# HandHeld_Terminal_V2_Rev3.net
KiCad netlist of a schematic drawn in Altium Designer
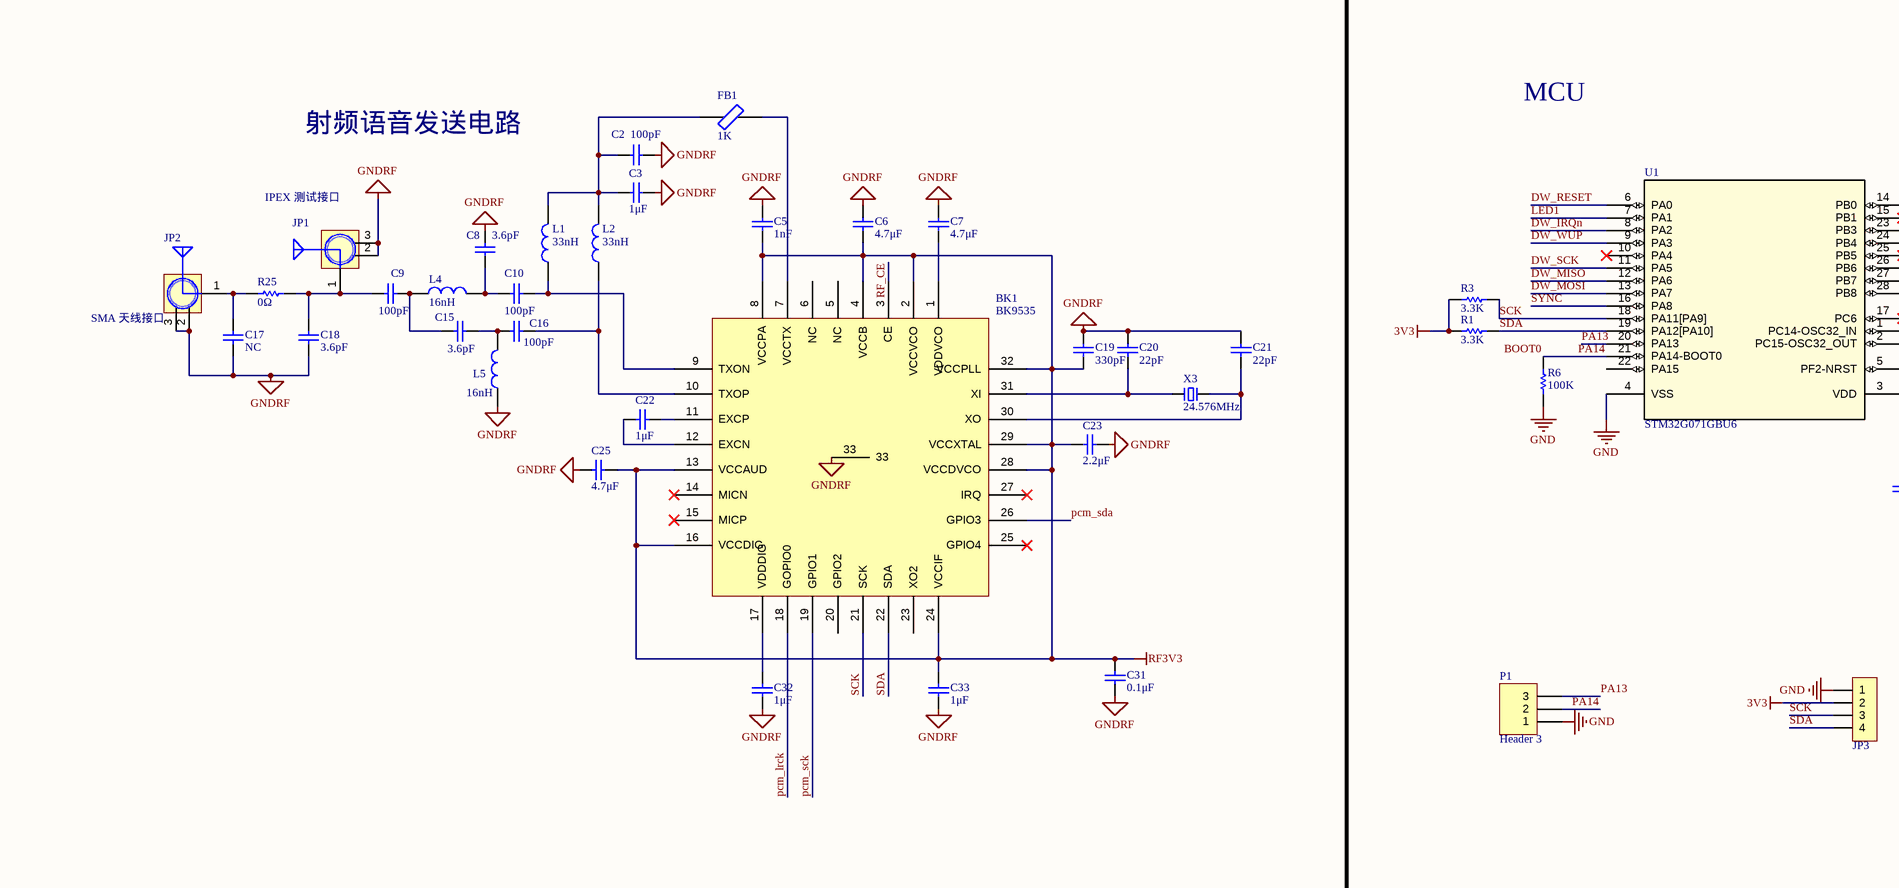
[diagram p0: HandHeld_Terminal_V2_Rev3.SchDoc, top left]
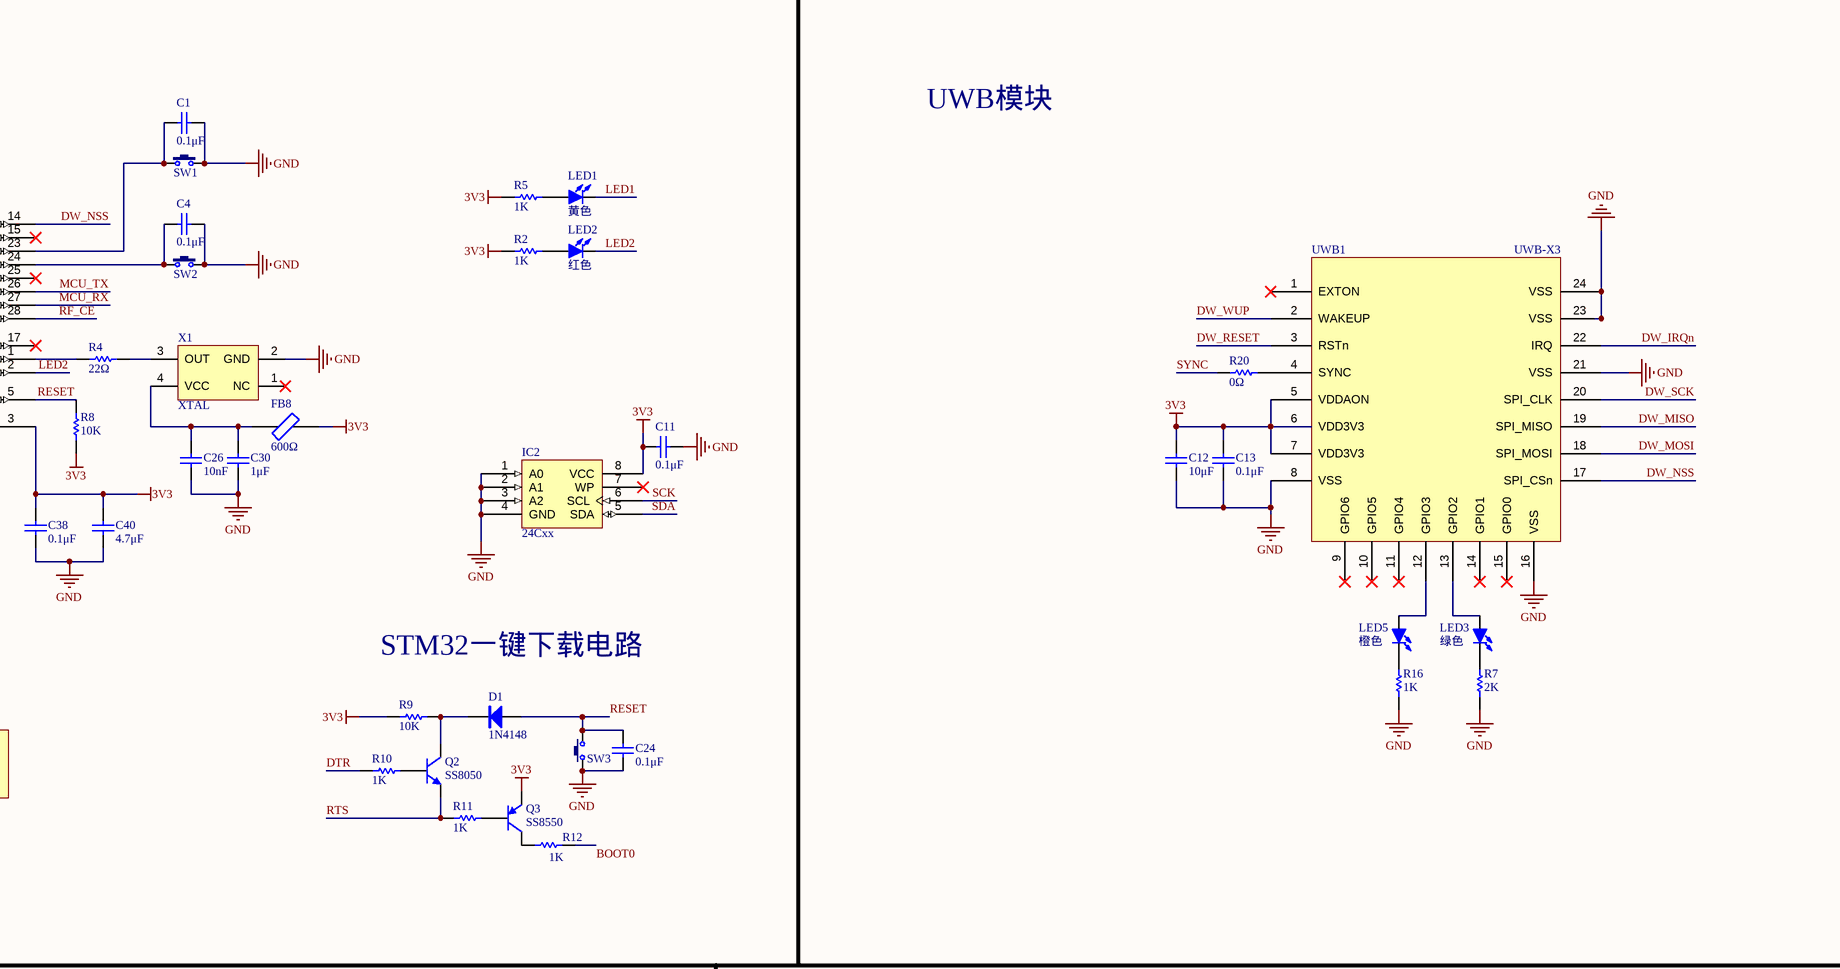
[diagram p1: HandHeld_Terminal_V2_Rev3.SchDoc, top right]
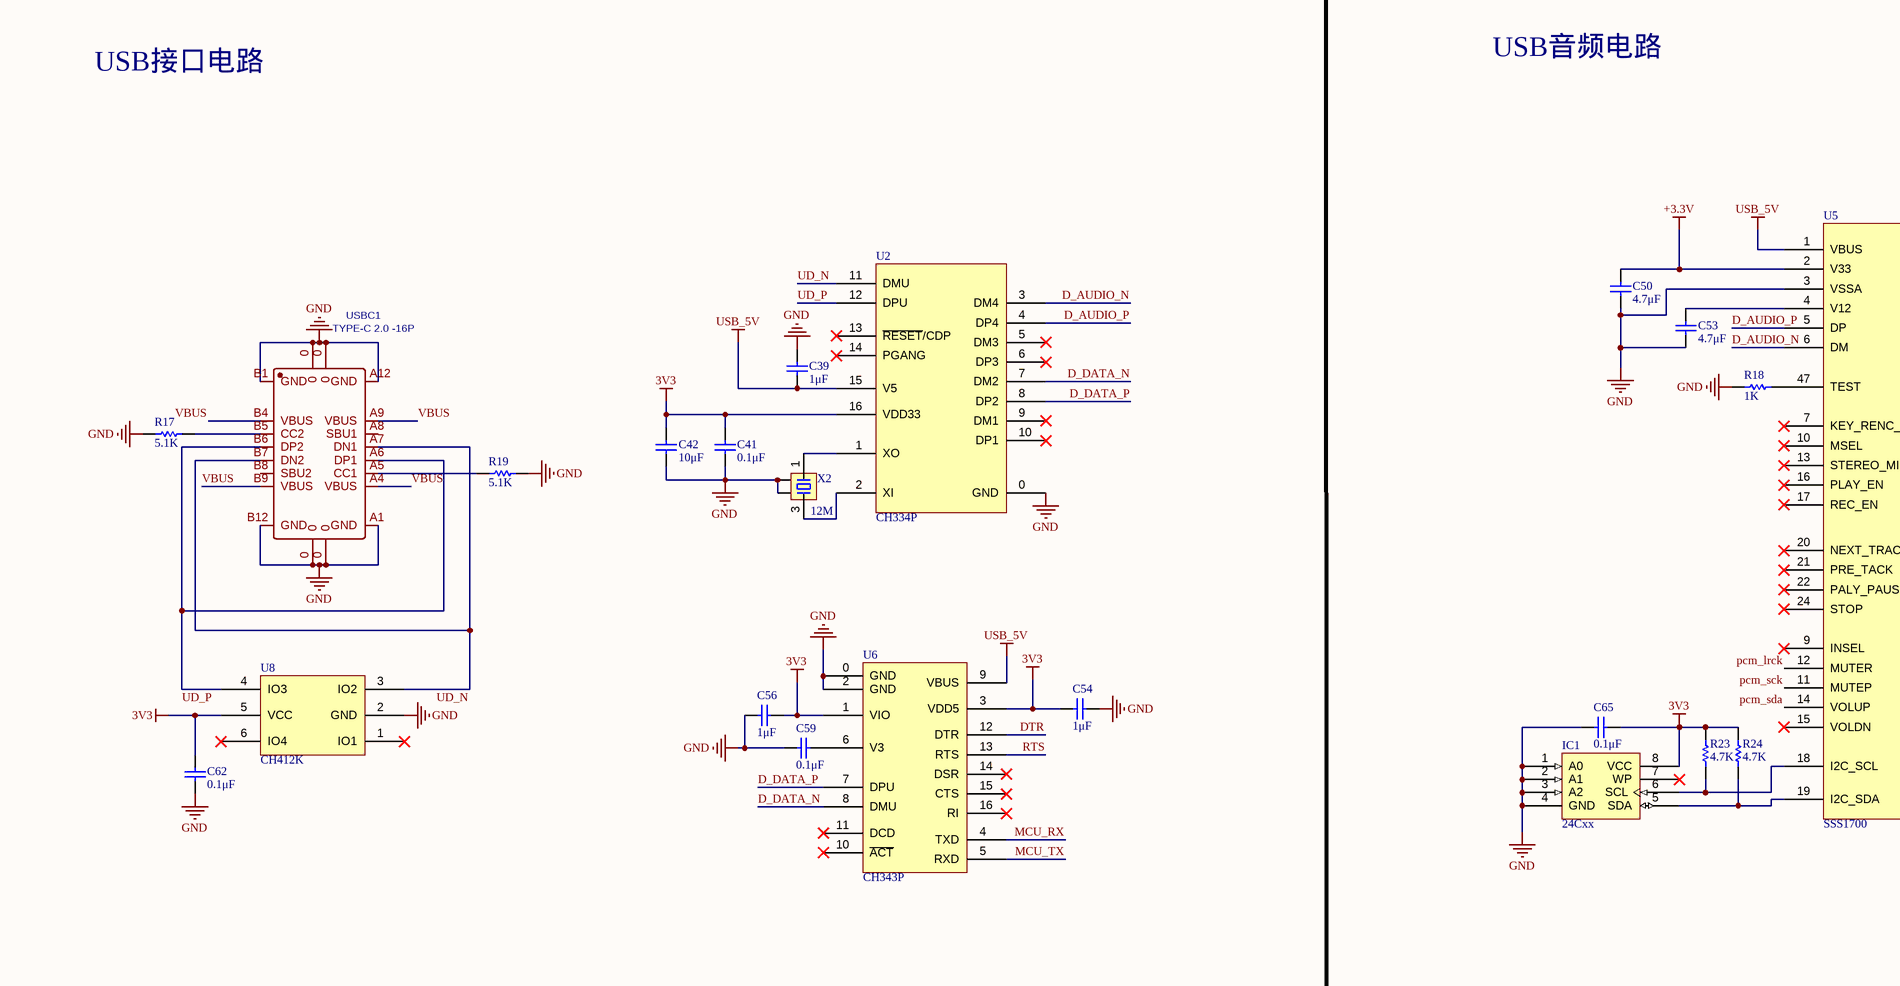
[diagram p2: HandHeld_Terminal_V2_Rev3.SchDoc, bottom left]
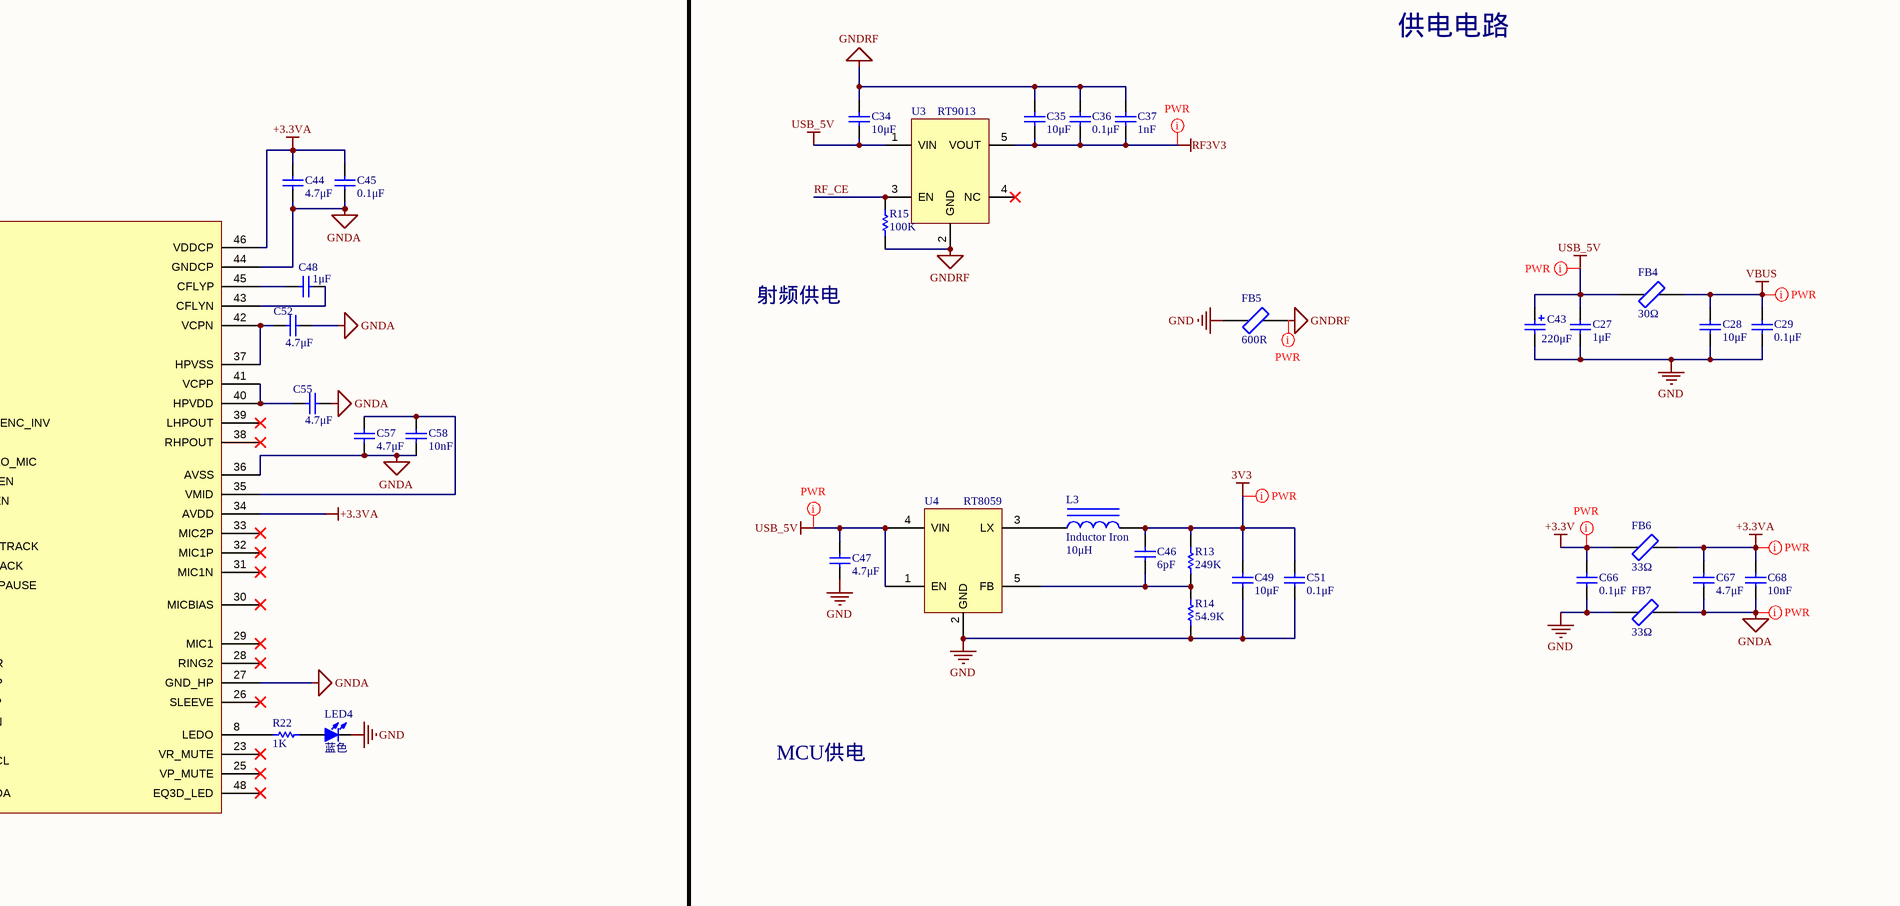
[diagram p3: HandHeld_Terminal_V2_Rev3.SchDoc, bottom right]

(export (version "E")
  (design (tool "Eeschema 10.0.6"))
  (components
    (comp (ref "BK1") (value "BK9535") (footprint "QFN32 5x5_N") (libsource (lib "Nixie") (part "BK9530")))
    (comp (ref "C1")
      (value "0.1μF")
      (footprint "C 0603_L")
      (description "Capacitor")
      (fields (field (name "Comment") "Cap") (field (name "PUBLISHER") "Altium Limited"))
      (libsource (lib "Nixie") (part "Cap"))
    )
    (comp (ref "C2")
      (value "100pF")
      (footprint "C 0603_L")
      (description "Capacitor")
      (fields (field (name "Comment") "Cap") (field (name "PUBLISHER") "Altium Limited"))
      (libsource (lib "Nixie") (part "Cap"))
    )
    (comp (ref "C3")
      (value "1μF")
      (footprint "C 0603_L")
      (description "Capacitor")
      (fields (field (name "Comment") "Cap") (field (name "PUBLISHER") "Altium Limited"))
      (libsource (lib "Nixie") (part "Cap"))
    )
    (comp (ref "C4")
      (value "0.1μF")
      (footprint "C 0603_L")
      (description "Capacitor")
      (fields (field (name "Comment") "Cap") (field (name "PUBLISHER") "Altium Limited"))
      (libsource (lib "Nixie") (part "Cap"))
    )
    (comp (ref "C5")
      (value "1nF")
      (footprint "C 0603_L")
      (description "Capacitor")
      (fields (field (name "Comment") "Cap") (field (name "PUBLISHER") "Altium Limited"))
      (libsource (lib "Nixie") (part "Cap"))
    )
    (comp (ref "C6")
      (value "4.7μF")
      (footprint "C 0603_L")
      (description "Capacitor")
      (fields (field (name "Comment") "Cap") (field (name "PUBLISHER") "Altium Limited"))
      (libsource (lib "Nixie") (part "Cap"))
    )
    (comp (ref "C7")
      (value "4.7μF")
      (footprint "C 0603_L")
      (description "Capacitor")
      (fields (field (name "Comment") "Cap") (field (name "PUBLISHER") "Altium Limited"))
      (libsource (lib "Nixie") (part "Cap"))
    )
    (comp (ref "C8")
      (value "3.6pF")
      (footprint "C 0603_L")
      (description "Capacitor")
      (fields (field (name "Comment") "Cap") (field (name "PUBLISHER") "Altium Limited"))
      (libsource (lib "Nixie") (part "Cap"))
    )
    (comp (ref "C9")
      (value "100pF")
      (footprint "C 0603_L")
      (description "Capacitor")
      (fields (field (name "Comment") "Cap") (field (name "PUBLISHER") "Altium Limited"))
      (libsource (lib "Nixie") (part "Cap"))
    )
    (comp (ref "C10")
      (value "100pF")
      (footprint "C 0603_L")
      (description "Capacitor")
      (fields (field (name "Comment") "Cap") (field (name "PUBLISHER") "Altium Limited"))
      (libsource (lib "Nixie") (part "Cap"))
    )
    (comp (ref "C11")
      (value "0.1μF")
      (footprint "C 0603_L")
      (description "Capacitor")
      (fields (field (name "Comment") "Cap") (field (name "PUBLISHER") "Altium Limited"))
      (libsource (lib "Nixie") (part "Cap"))
    )
    (comp (ref "C12")
      (value "10μF")
      (footprint "C 0603_L")
      (description "Capacitor")
      (fields (field (name "Comment") "Cap") (field (name "PUBLISHER") "Altium Limited"))
      (libsource (lib "Nixie") (part "Cap"))
    )
    (comp (ref "C13")
      (value "0.1μF")
      (footprint "C 0603_L")
      (description "Capacitor")
      (fields (field (name "Comment") "Cap") (field (name "PUBLISHER") "Altium Limited"))
      (libsource (lib "Nixie") (part "Cap"))
    )
    (comp (ref "C15")
      (value "3.6pF")
      (footprint "C 0603_L")
      (description "Capacitor")
      (fields (field (name "Comment") "Cap") (field (name "PUBLISHER") "Altium Limited"))
      (libsource (lib "Nixie") (part "Cap"))
    )
    (comp (ref "C16")
      (value "100pF")
      (footprint "C 0603_L")
      (description "Capacitor")
      (fields (field (name "Comment") "Cap") (field (name "PUBLISHER") "Altium Limited"))
      (libsource (lib "Nixie") (part "Cap"))
    )
    (comp (ref "C17")
      (value "NC")
      (footprint "C 0603_L")
      (description "Capacitor")
      (fields (field (name "Comment") "Cap") (field (name "PUBLISHER") "Altium Limited"))
      (libsource (lib "Nixie") (part "Cap"))
    )
    (comp (ref "C18")
      (value "3.6pF")
      (footprint "C 0603_L")
      (description "Capacitor")
      (fields (field (name "Comment") "Cap") (field (name "PUBLISHER") "Altium Limited"))
      (libsource (lib "Nixie") (part "Cap"))
    )
    (comp (ref "C19")
      (value "330pF")
      (footprint "C 0603_L")
      (description "Capacitor")
      (fields (field (name "Comment") "Cap") (field (name "PUBLISHER") "Altium Limited"))
      (libsource (lib "Nixie") (part "Cap"))
    )
    (comp (ref "C20")
      (value "22pF")
      (footprint "C 0603_L")
      (description "Capacitor")
      (fields (field (name "Comment") "Cap") (field (name "PUBLISHER") "Altium Limited"))
      (libsource (lib "Nixie") (part "Cap"))
    )
    (comp (ref "C21")
      (value "22pF")
      (footprint "C 0603_L")
      (description "Capacitor")
      (fields (field (name "Comment") "Cap") (field (name "PUBLISHER") "Altium Limited"))
      (libsource (lib "Nixie") (part "Cap"))
    )
    (comp (ref "C22")
      (value "1μF")
      (footprint "C 0603_L")
      (description "Capacitor")
      (fields (field (name "Comment") "Cap") (field (name "PUBLISHER") "Altium Limited"))
      (libsource (lib "Nixie") (part "Cap"))
    )
    (comp (ref "C23")
      (value "2.2μF")
      (footprint "C 0603_L")
      (description "Capacitor")
      (fields (field (name "Comment") "Cap") (field (name "PUBLISHER") "Altium Limited"))
      (libsource (lib "Nixie") (part "Cap"))
    )
    (comp (ref "C24")
      (value "0.1μF")
      (footprint "C 0603_L")
      (description "Capacitor")
      (fields (field (name "Comment") "Cap") (field (name "PUBLISHER") "Altium Limited"))
      (libsource (lib "Nixie") (part "Cap"))
    )
    (comp (ref "C25")
      (value "4.7μF")
      (footprint "C 0603_L")
      (description "Capacitor")
      (fields (field (name "Comment") "Cap") (field (name "PUBLISHER") "Altium Limited"))
      (libsource (lib "Nixie") (part "Cap"))
    )
    (comp (ref "C26")
      (value "10nF")
      (footprint "C 0603_L")
      (description "Capacitor")
      (fields (field (name "Comment") "Cap") (field (name "PUBLISHER") "Altium Limited"))
      (libsource (lib "Nixie") (part "Cap"))
    )
    (comp (ref "C27")
      (value "1μF")
      (footprint "C 0603_L")
      (description "Capacitor")
      (fields (field (name "Comment") "Cap") (field (name "PUBLISHER") "Altium Limited"))
      (libsource (lib "Nixie") (part "Cap"))
    )
    (comp (ref "C28")
      (value "10μF")
      (footprint "C 0603_L")
      (description "Capacitor")
      (fields (field (name "Comment") "Cap") (field (name "PUBLISHER") "Altium Limited"))
      (libsource (lib "Nixie") (part "Cap"))
    )
    (comp (ref "C29")
      (value "0.1μF")
      (footprint "C 0603_L")
      (description "Capacitor")
      (fields (field (name "Comment") "Cap") (field (name "PUBLISHER") "Altium Limited"))
      (libsource (lib "Nixie") (part "Cap"))
    )
    (comp (ref "C30")
      (value "1μF")
      (footprint "C 0603_L")
      (description "Capacitor")
      (fields (field (name "Comment") "Cap") (field (name "PUBLISHER") "Altium Limited"))
      (libsource (lib "Nixie") (part "Cap"))
    )
    (comp (ref "C31")
      (value "0.1μF")
      (footprint "C 0603_L")
      (description "Capacitor")
      (fields (field (name "Comment") "Cap") (field (name "PUBLISHER") "Altium Limited"))
      (libsource (lib "Nixie") (part "Cap"))
    )
    (comp (ref "C32")
      (value "1μF")
      (footprint "C 0603_L")
      (description "Capacitor")
      (fields (field (name "Comment") "Cap") (field (name "PUBLISHER") "Altium Limited"))
      (libsource (lib "Nixie") (part "Cap"))
    )
    (comp (ref "C33")
      (value "1μF")
      (footprint "C 0603_L")
      (description "Capacitor")
      (fields (field (name "Comment") "Cap") (field (name "PUBLISHER") "Altium Limited"))
      (libsource (lib "Nixie") (part "Cap"))
    )
    (comp (ref "C34")
      (value "10μF")
      (footprint "C 0603_L")
      (description "Capacitor")
      (fields (field (name "Comment") "Cap") (field (name "PUBLISHER") "Altium Limited"))
      (libsource (lib "Nixie") (part "Cap"))
    )
    (comp (ref "C35")
      (value "10μF")
      (footprint "C 0603_L")
      (description "Capacitor")
      (fields (field (name "Comment") "Cap") (field (name "PUBLISHER") "Altium Limited"))
      (libsource (lib "Nixie") (part "Cap"))
    )
    (comp (ref "C36")
      (value "0.1μF")
      (footprint "C 0603_L")
      (description "Capacitor")
      (fields (field (name "Comment") "Cap") (field (name "PUBLISHER") "Altium Limited"))
      (libsource (lib "Nixie") (part "Cap"))
    )
    (comp (ref "C37")
      (value "1nF")
      (footprint "C 0603_L")
      (description "Capacitor")
      (fields (field (name "Comment") "Cap") (field (name "PUBLISHER") "Altium Limited"))
      (libsource (lib "Nixie") (part "Cap"))
    )
    (comp (ref "C38")
      (value "0.1μF")
      (footprint "C 0603_L")
      (description "Capacitor")
      (fields (field (name "Comment") "Cap") (field (name "PUBLISHER") "Altium Limited"))
      (libsource (lib "Nixie") (part "Cap"))
    )
    (comp (ref "C39")
      (value "1μF")
      (footprint "C 0603_L")
      (description "Capacitor")
      (fields (field (name "Comment") "Cap") (field (name "PUBLISHER") "Altium Limited"))
      (libsource (lib "Nixie") (part "Cap"))
    )
    (comp (ref "C40")
      (value "4.7μF")
      (footprint "C 0603_L")
      (description "Capacitor")
      (fields (field (name "Comment") "Cap") (field (name "PUBLISHER") "Altium Limited"))
      (libsource (lib "Nixie") (part "Cap"))
    )
    (comp (ref "C41")
      (value "0.1μF")
      (footprint "C 0603_L")
      (description "Capacitor")
      (fields (field (name "Comment") "Cap") (field (name "PUBLISHER") "Altium Limited"))
      (libsource (lib "Nixie") (part "Cap"))
    )
    (comp (ref "C42")
      (value "10μF")
      (footprint "C 0603_L")
      (description "Capacitor")
      (fields (field (name "Comment") "Cap") (field (name "PUBLISHER") "Altium Limited"))
      (libsource (lib "Nixie") (part "Cap"))
    )
    (comp (ref "C43")
      (value "220μF")
      (footprint "CM D(6.3*5.4)")
      (description "Polarized Capacitor (Radial)")
      (fields (field (name "Comment") "Cap Pol1") (field (name "PUBLISHER") "Altium Limited"))
      (libsource (lib "Nixie") (part "Cap Pol1"))
    )
    (comp (ref "C44")
      (value "4.7μF")
      (footprint "C 0603_L")
      (description "Capacitor")
      (fields (field (name "Comment") "Cap") (field (name "PUBLISHER") "Altium Limited"))
      (libsource (lib "Nixie") (part "Cap"))
    )
    (comp (ref "C45")
      (value "0.1μF")
      (footprint "C 0603_L")
      (description "Capacitor")
      (fields (field (name "Comment") "Cap") (field (name "PUBLISHER") "Altium Limited"))
      (libsource (lib "Nixie") (part "Cap"))
    )
    (comp (ref "C46")
      (value "6pF")
      (footprint "C 0603_L")
      (description "Capacitor")
      (fields (field (name "Comment") "Cap") (field (name "PUBLISHER") "Altium Limited"))
      (libsource (lib "Nixie") (part "Cap"))
    )
    (comp (ref "C47")
      (value "4.7μF")
      (footprint "C 0603_L")
      (description "Capacitor")
      (fields (field (name "Comment") "Cap") (field (name "PUBLISHER") "Altium Limited"))
      (libsource (lib "Nixie") (part "Cap"))
    )
    (comp (ref "C48")
      (value "1μF")
      (footprint "C 0603_L")
      (description "Capacitor")
      (fields (field (name "Comment") "Cap") (field (name "PUBLISHER") "Altium Limited"))
      (libsource (lib "Nixie") (part "Cap"))
    )
    (comp (ref "C49")
      (value "10μF")
      (footprint "C 0603_L")
      (description "Capacitor")
      (fields (field (name "Comment") "Cap") (field (name "PUBLISHER") "Altium Limited"))
      (libsource (lib "Nixie") (part "Cap"))
    )
    (comp (ref "C50")
      (value "4.7μF")
      (footprint "C 0603_L")
      (description "Capacitor")
      (fields (field (name "Comment") "Cap") (field (name "PUBLISHER") "Altium Limited"))
      (libsource (lib "Nixie") (part "Cap"))
    )
    (comp (ref "C51")
      (value "0.1μF")
      (footprint "C 0603_L")
      (description "Capacitor")
      (fields (field (name "Comment") "Cap") (field (name "PUBLISHER") "Altium Limited"))
      (libsource (lib "Nixie") (part "Cap"))
    )
    (comp (ref "C52")
      (value "4.7μF")
      (footprint "C 0603_L")
      (description "Capacitor")
      (fields (field (name "Comment") "Cap") (field (name "PUBLISHER") "Altium Limited"))
      (libsource (lib "Nixie") (part "Cap"))
    )
    (comp (ref "C53")
      (value "4.7μF")
      (footprint "C 0603_L")
      (description "Capacitor")
      (fields (field (name "Comment") "Cap") (field (name "PUBLISHER") "Altium Limited"))
      (libsource (lib "Nixie") (part "Cap"))
    )
    (comp (ref "C54")
      (value "1μF")
      (footprint "C 0603_L")
      (description "Capacitor")
      (fields (field (name "Comment") "Cap") (field (name "PUBLISHER") "Altium Limited"))
      (libsource (lib "Nixie") (part "Cap"))
    )
    (comp (ref "C55")
      (value "4.7μF")
      (footprint "C 0603_L")
      (description "Capacitor")
      (fields (field (name "Comment") "Cap") (field (name "PUBLISHER") "Altium Limited"))
      (libsource (lib "Nixie") (part "Cap"))
    )
    (comp (ref "C56")
      (value "1μF")
      (footprint "C 0603_L")
      (description "Capacitor")
      (fields (field (name "Comment") "Cap") (field (name "PUBLISHER") "Altium Limited"))
      (libsource (lib "Nixie") (part "Cap"))
    )
    (comp (ref "C57")
      (value "4.7μF")
      (footprint "C 0603_L")
      (description "Capacitor")
      (fields (field (name "Comment") "Cap") (field (name "PUBLISHER") "Altium Limited"))
      (libsource (lib "Nixie") (part "Cap"))
    )
    (comp (ref "C58")
      (value "10nF")
      (footprint "C 0603_L")
      (description "Capacitor")
      (fields (field (name "Comment") "Cap") (field (name "PUBLISHER") "Altium Limited"))
      (libsource (lib "Nixie") (part "Cap"))
    )
    (comp (ref "C59")
      (value "0.1μF")
      (footprint "C 0603_L")
      (description "Capacitor")
      (fields (field (name "Comment") "Cap") (field (name "PUBLISHER") "Altium Limited"))
      (libsource (lib "Nixie") (part "Cap"))
    )
    (comp (ref "C62")
      (value "0.1μF")
      (footprint "C 0603_L")
      (description "Capacitor")
      (fields (field (name "Comment") "Cap") (field (name "PUBLISHER") "Altium Limited"))
      (libsource (lib "Nixie") (part "Cap"))
    )
    (comp (ref "C65")
      (value "0.1μF")
      (footprint "C 0603_L")
      (description "Capacitor")
      (fields (field (name "Comment") "Cap") (field (name "PUBLISHER") "Altium Limited"))
      (libsource (lib "Nixie") (part "Cap"))
    )
    (comp (ref "C66")
      (value "0.1μF")
      (footprint "C 0603_L")
      (description "Capacitor")
      (fields (field (name "Comment") "Cap") (field (name "PUBLISHER") "Altium Limited"))
      (libsource (lib "Nixie") (part "Cap"))
    )
    (comp (ref "C67")
      (value "4.7μF")
      (footprint "C 0603_L")
      (description "Capacitor")
      (fields (field (name "Comment") "Cap") (field (name "PUBLISHER") "Altium Limited"))
      (libsource (lib "Nixie") (part "Cap"))
    )
    (comp (ref "C68")
      (value "10nF")
      (footprint "C 0603_L")
      (description "Capacitor")
      (fields (field (name "Comment") "Cap") (field (name "PUBLISHER") "Altium Limited"))
      (libsource (lib "Nixie") (part "Cap"))
    )
    (comp (ref "D1")
      (value "1N4148")
      (footprint "SOD-323")
      (description "开关二极管")
      (libsource (lib "Nixie") (part "1N4148"))
    )
    (comp (ref "FB1")
      (value "1K")
      (footprint "C 0603_L")
      (description "铁氧体磁珠")
      (fields (field (name "Comment") "Ferrite bead"))
      (libsource (lib "Nixie") (part "Ferrite bead"))
    )
    (comp (ref "FB4")
      (value "30Ω")
      (footprint "C 0603_L")
      (description "铁氧体磁珠")
      (fields (field (name "Comment") "Ferrite bead"))
      (libsource (lib "Nixie") (part "Ferrite bead"))
    )
    (comp (ref "FB5")
      (value "600R")
      (footprint "C 0805_L")
      (description "铁氧体磁珠")
      (fields (field (name "Comment") "Ferrite bead"))
      (libsource (lib "Nixie") (part "Ferrite bead"))
    )
    (comp (ref "FB6")
      (value "33Ω")
      (footprint "C 0603_L")
      (description "铁氧体磁珠")
      (fields (field (name "Comment") "Ferrite bead"))
      (libsource (lib "Nixie") (part "Ferrite bead"))
    )
    (comp (ref "FB7")
      (value "33Ω")
      (footprint "C 0603_L")
      (description "铁氧体磁珠")
      (fields (field (name "Comment") "Ferrite bead"))
      (libsource (lib "Nixie") (part "Ferrite bead"))
    )
    (comp (ref "FB8")
      (value "600Ω")
      (footprint "C 0603_L")
      (description "铁氧体磁珠")
      (fields (field (name "Comment") "Ferrite bead"))
      (libsource (lib "Nixie") (part "Ferrite bead"))
    )
    (comp (ref "IC1")
      (value "24Cxx")
      (footprint "SOP8_L")
      (description "外置EEPROM")
      (fields (field (name "版权归属") "封装库来自淘宝 ID：黄晶宝石"))
      (libsource (lib "Nixie") (part "24Cxx"))
    )
    (comp (ref "IC2")
      (value "24Cxx")
      (footprint "SOP8_L")
      (description "外置EEPROM")
      (fields (field (name "版权归属") "封装库来自淘宝 ID：黄晶宝石"))
      (libsource (lib "Nixie") (part "24Cxx"))
    )
    (comp (ref "JP1")
      (value "IPEX 测试接口")
      (footprint "COAXIAL/SMD/CON/V/I-PEX/W08-5801")
      (description "SMA-2.4G射频天线接口")
      (fields (field (name "版权归属") "封装库来自淘宝 ID：黄晶宝石"))
      (libsource (lib "") (part "SMA_1"))
    )
    (comp (ref "JP2")
      (value "SMA 天线接口")
      (footprint "SMA-KE")
      (description "SMA-2.4G射频天线接口")
      (fields (field (name "版权归属") "封装库来自淘宝 ID：黄晶宝石"))
      (libsource (lib "Nixie") (part "SMA"))
    )
    (comp (ref "JP3")
      (value "HDR-1X4")
      (footprint "HDR2.54-M-LI-4P")
      (description "4P接插件")
      (fields (field (name "版权归属") "封装库来自淘宝 ID：黄晶宝石"))
      (libsource (lib "Nixie") (part "Header 4"))
    )
    (comp (ref "L1")
      (value "33nH")
      (footprint "L 0603")
      (description "小功率贴片电感")
      (fields (field (name "Comment") "L"))
      (libsource (lib "Nixie") (part "L"))
    )
    (comp (ref "L2")
      (value "33nH")
      (footprint "L 0603")
      (description "小功率贴片电感")
      (fields (field (name "Comment") "L"))
      (libsource (lib "Nixie") (part "L"))
    )
    (comp (ref "L3")
      (value "Inductor Iron")
      (footprint "NR4018")
      (description "Magnetic-Core Inductor")
      (fields (field (name "ALTIUM_VALUE") "10μH") (field (name "PUBLISHER") "Altium Limited"))
      (libsource (lib "Nixie") (part "Inductor Iron"))
    )
    (comp (ref "L4")
      (value "16nH")
      (footprint "L 0603")
      (description "小功率贴片电感")
      (fields (field (name "Comment") "L"))
      (libsource (lib "Nixie") (part "L"))
    )
    (comp (ref "L5")
      (value "16nH")
      (footprint "L 0603")
      (description "小功率贴片电感")
      (fields (field (name "Comment") "L"))
      (libsource (lib "Nixie") (part "L"))
    )
    (comp (ref "LED1")
      (value "黄色")
      (footprint "LED 0805G")
      (description "贴片LED")
      (fields (field (name "版权归属") "封装库来自淘宝 ID：黄晶宝石"))
      (libsource (lib "Nixie") (part "LED-SMD"))
    )
    (comp (ref "LED2")
      (value "红色")
      (footprint "LED 0805R")
      (description "贴片LED")
      (fields (field (name "版权归属") "封装库来自淘宝 ID：黄晶宝石"))
      (libsource (lib "Nixie") (part "LED-SMD"))
    )
    (comp (ref "LED3")
      (value "绿色")
      (footprint "LED 0805G")
      (description "贴片LED")
      (fields (field (name "版权归属") "封装库来自淘宝 ID：黄晶宝石"))
      (libsource (lib "Nixie") (part "LED-SMD"))
    )
    (comp (ref "LED4")
      (value "蓝色")
      (footprint "LED 0805B")
      (description "贴片LED")
      (fields (field (name "版权归属") "封装库来自淘宝 ID：黄晶宝石"))
      (libsource (lib "Nixie") (part "LED-SMD"))
    )
    (comp (ref "LED5")
      (value "橙色")
      (footprint "LED 0805G")
      (description "贴片LED")
      (fields (field (name "版权归属") "封装库来自淘宝 ID：黄晶宝石"))
      (libsource (lib "Nixie") (part "LED-SMD"))
    )
    (comp (ref "P1")
      (value "Header 3")
      (footprint "HDR2.54-LI-3P")
      (description "Header, 3-Pin")
      (fields (field (name "PUBLISHER") "Altium Limited"))
      (libsource (lib "Miscellaneous Connectors") (part "Header 3"))
    )
    (comp (ref "Q2")
      (value "SS8050")
      (footprint "SOT-23-3L")
      (description "高频放大-NPN型")
      (fields (field (name "版权归属") "封装库来自淘宝 ID：黄晶宝石"))
      (libsource (lib "Nixie") (part "8050-SMD"))
    )
    (comp (ref "Q3")
      (value "SS8550")
      (footprint "SOT-23-3L")
      (description "高频放大-PNP型")
      (fields (field (name "版权归属") "封装库来自淘宝 ID：黄晶宝石"))
      (libsource (lib "Nixie") (part "8550-SMD"))
    )
    (comp (ref "R1")
      (value "3.3K")
      (footprint "R 0603_L")
      (description "Resistor")
      (fields (field (name "PUBLISHER") "Altium Limited"))
      (libsource (lib "Nixie") (part "Resistor"))
    )
    (comp (ref "R2")
      (value "1K")
      (footprint "R 0603_L")
      (description "Resistor")
      (fields (field (name "PUBLISHER") "Altium Limited"))
      (libsource (lib "Nixie") (part "Resistor"))
    )
    (comp (ref "R3")
      (value "3.3K")
      (footprint "R 0603_L")
      (description "Resistor")
      (fields (field (name "PUBLISHER") "Altium Limited"))
      (libsource (lib "Nixie") (part "Resistor"))
    )
    (comp (ref "R4")
      (value "22Ω")
      (footprint "R 0603_L")
      (description "Resistor")
      (fields (field (name "PUBLISHER") "Altium Limited"))
      (libsource (lib "Nixie") (part "Resistor"))
    )
    (comp (ref "R5")
      (value "1K")
      (footprint "R 0603_L")
      (description "Resistor")
      (fields (field (name "PUBLISHER") "Altium Limited"))
      (libsource (lib "Nixie") (part "Resistor"))
    )
    (comp (ref "R6")
      (value "100K")
      (footprint "R 0603_L")
      (description "Resistor")
      (fields (field (name "PUBLISHER") "Altium Limited"))
      (libsource (lib "Nixie") (part "Resistor"))
    )
    (comp (ref "R7")
      (value "2K")
      (footprint "R 0603_L")
      (description "Resistor")
      (fields (field (name "PUBLISHER") "Altium Limited"))
      (libsource (lib "Nixie") (part "Resistor"))
    )
    (comp (ref "R8")
      (value "10K")
      (footprint "R 0603_L")
      (description "Resistor")
      (fields (field (name "PUBLISHER") "Altium Limited"))
      (libsource (lib "Nixie") (part "Resistor"))
    )
    (comp (ref "R9")
      (value "10K")
      (footprint "R 0603_L")
      (description "Resistor")
      (fields (field (name "PUBLISHER") "Altium Limited"))
      (libsource (lib "Nixie") (part "Resistor"))
    )
    (comp (ref "R10")
      (value "1K")
      (footprint "R 0603_L")
      (description "Resistor")
      (fields (field (name "PUBLISHER") "Altium Limited"))
      (libsource (lib "Nixie") (part "Resistor"))
    )
    (comp (ref "R11")
      (value "1K")
      (footprint "R 0603_L")
      (description "Resistor")
      (fields (field (name "PUBLISHER") "Altium Limited"))
      (libsource (lib "Nixie") (part "Resistor"))
    )
    (comp (ref "R12")
      (value "1K")
      (footprint "R 0603_L")
      (description "Resistor")
      (fields (field (name "PUBLISHER") "Altium Limited"))
      (libsource (lib "Nixie") (part "Resistor"))
    )
    (comp (ref "R13")
      (value "249K")
      (footprint "R 0603_L")
      (description "Resistor")
      (fields (field (name "PUBLISHER") "Altium Limited"))
      (libsource (lib "Nixie") (part "Resistor"))
    )
    (comp (ref "R14")
      (value "54.9K")
      (footprint "R 0603_L")
      (description "Resistor")
      (fields (field (name "PUBLISHER") "Altium Limited"))
      (libsource (lib "Nixie") (part "Resistor"))
    )
    (comp (ref "R15")
      (value "100K")
      (footprint "R 0603_L")
      (description "Resistor")
      (fields (field (name "PUBLISHER") "Altium Limited"))
      (libsource (lib "Nixie") (part "Resistor"))
    )
    (comp (ref "R16")
      (value "1K")
      (footprint "R 0603_L")
      (description "Resistor")
      (fields (field (name "PUBLISHER") "Altium Limited"))
      (libsource (lib "Nixie") (part "Resistor"))
    )
    (comp (ref "R17")
      (value "5.1K")
      (footprint "R 0603_L")
      (description "Resistor")
      (fields (field (name "PUBLISHER") "Altium Limited"))
      (libsource (lib "Nixie") (part "Resistor"))
    )
    (comp (ref "R18")
      (value "1K")
      (footprint "R 0603_L")
      (description "Resistor")
      (fields (field (name "PUBLISHER") "Altium Limited"))
      (libsource (lib "Nixie") (part "Resistor"))
    )
    (comp (ref "R19")
      (value "5.1K")
      (footprint "R 0603_L")
      (description "Resistor")
      (fields (field (name "PUBLISHER") "Altium Limited"))
      (libsource (lib "Nixie") (part "Resistor"))
    )
    (comp (ref "R20")
      (value "0Ω")
      (footprint "R 0603_L")
      (description "Resistor")
      (fields (field (name "PUBLISHER") "Altium Limited"))
      (libsource (lib "Nixie") (part "Resistor"))
    )
    (comp (ref "R22")
      (value "1K")
      (footprint "R 0603_L")
      (description "Resistor")
      (fields (field (name "PUBLISHER") "Altium Limited"))
      (libsource (lib "Nixie") (part "Resistor"))
    )
    (comp (ref "R23")
      (value "4.7K")
      (footprint "R 0603_L")
      (description "Resistor")
      (fields (field (name "PUBLISHER") "Altium Limited"))
      (libsource (lib "Nixie") (part "Resistor"))
    )
    (comp (ref "R24")
      (value "4.7K")
      (footprint "R 0603_L")
      (description "Resistor")
      (fields (field (name "PUBLISHER") "Altium Limited"))
      (libsource (lib "Nixie") (part "Resistor"))
    )
    (comp (ref "R25")
      (value "0Ω")
      (footprint "R 0603_L")
      (description "Resistor")
      (fields (field (name "PUBLISHER") "Altium Limited"))
      (libsource (lib "Nixie") (part "Resistor"))
    )
    (comp (ref "SW1")
      (value "3x6x5")
      (footprint "TSW SMD-3*6*2.5")
      (description "3x6轻触开关")
      (fields (field (name "版权归属") "封装库来自淘宝 ID：黄晶宝石"))
      (libsource (lib "Nixie") (part "TSW 3x6"))
    )
    (comp (ref "SW2")
      (value "3x6x5")
      (footprint "TSW SMD-3*6*2.5")
      (description "3x6轻触开关")
      (fields (field (name "版权归属") "封装库来自淘宝 ID：黄晶宝石"))
      (libsource (lib "Nixie") (part "TSW 3x6"))
    )
    (comp (ref "SW3")
      (value "3x6x5")
      (footprint "TSW SMD-3*6*2.5")
      (description "3x6轻触开关")
      (fields (field (name "版权归属") "封装库来自淘宝 ID：黄晶宝石"))
      (libsource (lib "") (part "TSW 3x6_1"))
    )
    (comp (ref "U1")
      (value "STM32G071GBU6")
      (footprint "UFQFPN-28")
      (description "No Description Available")
      (libsource (lib "Nixie") (part "STM32G071GBU6"))
    )
    (comp (ref "U2")
      (value "CH334P")
      (footprint "QFN16")
      (description "4路usb_hub")
      (libsource (lib "Nixie") (part "CH334"))
    )
    (comp (ref "U3")
      (value "RT9013")
      (footprint "SOT23-5L")
      (description "LDO")
      (libsource (lib "HandHeld_terminal") (part "RT9013"))
    )
    (comp (ref "U4")
      (value "RT8059")
      (footprint "SOT23-5L")
      (description "DC-DC, 2.8-5.5V,1A")
      (libsource (lib "Nixie") (part "RT8059"))
    )
    (comp (ref "U5")
      (value "SSS1700")
      (footprint "LQFP48_L")
      (description "USB音频芯片")
      (libsource (lib "Nixie") (part "SSS1700"))
    )
    (comp (ref "U6")
      (value "CH343P")
      (footprint "QFN16")
      (description "USB转串口")
      (libsource (lib "Nixie") (part "CH343"))
    )
    (comp (ref "U8")
      (value "CH412K")
      (footprint "SOT-363")
      (description "四路ESD保护")
      (libsource (lib "Nixie") (part "CH412K"))
    )
    (comp (ref "USBC1")
      (value "TYPE-C 2.0 -16P")
      (footprint "USB-C-SMD_TYPE-C-USB-5")
      (description "USB2.0 Type-C 母座 16Pin")
      (libsource (lib "Nixie") (part "USB2.0 Type-C 16Pin母座"))
    )
    (comp (ref "UWB1")
      (value "UWB-X3")
      (footprint "UWB-X3-MAX-IPEX")
      (libsource (lib "Nixie") (part "UWB-X3(DWM3000)"))
    )
    (comp (ref "X1")
      (value "XTAL")
      (footprint "OSC 3225-4P")
      (description "4脚有源晶振")
      (libsource (lib "Nixie") (part "XTAL"))
    )
    (comp (ref "X2")
      (value "12M")
      (footprint "OSC 3225-4P")
      (description "4脚无源晶振")
      (fields (field (name "版权归属") "封装库来自淘宝卖家 ID：黄晶宝石"))
      (libsource (lib "Nixie") (part "XTAL-4P"))
    )
    (comp (ref "X3")
      (value "24.576MHz")
      (footprint "OSC 5032-2P")
      (description "2脚无源脚晶振")
      (fields (field (name "版权归属") "封装库来自淘宝卖家 ID：黄晶宝石"))
      (libsource (lib "Nixie") (part "XTAL-2P"))
    )
  )
  (nets
    (net (code "1") (name "+3.3V") (class "Default")
      (node (ref "C50") (pin "2") (pinfunction "2_2") (pintype "passive"))
      (node (ref "C66") (pin "2") (pinfunction "2_2") (pintype "passive"))
      (node (ref "FB6") (pin "1") (pinfunction "1_1") (pintype "passive"))
      (node (ref "U5") (pin "2") (pinfunction "V33_2") (pintype "passive"))
    )
    (net (code "2") (name "+3.3VA") (class "Default")
      (node (ref "C44") (pin "2") (pinfunction "2_2") (pintype "passive"))
      (node (ref "C45") (pin "2") (pinfunction "2_2") (pintype "passive"))
      (node (ref "C67") (pin "2") (pinfunction "2_2") (pintype "passive"))
      (node (ref "C68") (pin "2") (pinfunction "2_2") (pintype "passive"))
      (node (ref "FB6") (pin "2") (pinfunction "2_2") (pintype "passive"))
      (node (ref "U5") (pin "34") (pinfunction "AVDD_34") (pintype "passive"))
      (node (ref "U5") (pin "46") (pinfunction "VDDCP_46") (pintype "passive"))
    )
    (net (code "3") (name "/BOOT0") (class "Default")
      (node (ref "P1") (pin "2") (pinfunction "2_2") (pintype "passive"))
      (node (ref "R12") (pin "2") (pinfunction "2_2") (pintype "passive"))
      (node (ref "R6") (pin "1") (pinfunction "1_1") (pintype "passive"))
      (node (ref "U1") (pin "21") (pinfunction "PA14-BOOT0_21") (pintype "bidirectional"))
    )
    (net (code "4") (name "/DTR") (class "Default")
      (node (ref "R10") (pin "1") (pinfunction "1_1") (pintype "passive"))
      (node (ref "U6") (pin "12") (pinfunction "DTR_12") (pintype "passive"))
    )
    (net (code "5") (name "/DW_IRQn") (class "Default")
      (node (ref "U1") (pin "8") (pinfunction "PA2_8") (pintype "bidirectional"))
      (node (ref "UWB1") (pin "22") (pinfunction "IRQ_22") (pintype "passive"))
    )
    (net (code "6") (name "/DW_MISO") (class "Default")
      (node (ref "U1") (pin "12") (pinfunction "PA6_12") (pintype "bidirectional"))
      (node (ref "UWB1") (pin "19") (pinfunction "SPI_MISO_19") (pintype "passive"))
    )
    (net (code "7") (name "/DW_MOSI") (class "Default")
      (node (ref "U1") (pin "13") (pinfunction "PA7_13") (pintype "bidirectional"))
      (node (ref "UWB1") (pin "18") (pinfunction "SPI_MOSI_18") (pintype "passive"))
    )
    (net (code "8") (name "/DW_NSS") (class "Default")
      (node (ref "U1") (pin "14") (pinfunction "PB0_14") (pintype "bidirectional"))
      (node (ref "UWB1") (pin "17") (pinfunction "SPI_CSn_17") (pintype "passive"))
    )
    (net (code "9") (name "/DW_RESET") (class "Default")
      (node (ref "U1") (pin "6") (pinfunction "PA0_6") (pintype "bidirectional"))
      (node (ref "UWB1") (pin "3") (pinfunction "RSTn_3") (pintype "passive"))
    )
    (net (code "10") (name "/DW_SCK") (class "Default")
      (node (ref "U1") (pin "11") (pinfunction "PA5_11") (pintype "bidirectional"))
      (node (ref "UWB1") (pin "20") (pinfunction "SPI_CLK_20") (pintype "passive"))
    )
    (net (code "11") (name "/DW_WUP") (class "Default")
      (node (ref "U1") (pin "9") (pinfunction "PA3_9") (pintype "bidirectional"))
      (node (ref "UWB1") (pin "2") (pinfunction "WAKEUP_2") (pintype "passive"))
    )
    (net (code "12") (name "/D_AUDIO_N") (class "Default")
      (node (ref "U2") (pin "3") (pinfunction "DM4_3") (pintype "passive"))
      (node (ref "U5") (pin "6") (pinfunction "DM_6") (pintype "passive"))
    )
    (net (code "13") (name "/D_AUDIO_P") (class "Default")
      (node (ref "U2") (pin "4") (pinfunction "DP4_4") (pintype "passive"))
      (node (ref "U5") (pin "5") (pinfunction "DP_5") (pintype "passive"))
    )
    (net (code "14") (name "/D_DATA_N") (class "Default")
      (node (ref "U2") (pin "7") (pinfunction "DM2_7") (pintype "passive"))
      (node (ref "U6") (pin "8") (pinfunction "DMU_8") (pintype "passive"))
    )
    (net (code "15") (name "/D_DATA_P") (class "Default")
      (node (ref "U2") (pin "8") (pinfunction "DP2_8") (pintype "passive"))
      (node (ref "U6") (pin "7") (pinfunction "DPU_7") (pintype "passive"))
    )
    (net (code "16") (name "/LED1") (class "Default")
      (node (ref "LED1") (pin "2") (pinfunction "K_2") (pintype "passive"))
      (node (ref "U1") (pin "7") (pinfunction "PA1_7") (pintype "bidirectional"))
    )
    (net (code "17") (name "/LED2") (class "Default")
      (node (ref "LED2") (pin "2") (pinfunction "K_2") (pintype "passive"))
      (node (ref "U1") (pin "2") (pinfunction "PC15-OSC32_OUT_2") (pintype "bidirectional"))
    )
    (net (code "18") (name "/MCU_RX") (class "Default")
      (node (ref "U1") (pin "27") (pinfunction "PB7_27") (pintype "bidirectional"))
      (node (ref "U6") (pin "4") (pinfunction "TXD_4") (pintype "passive"))
    )
    (net (code "19") (name "/MCU_TX") (class "Default")
      (node (ref "U1") (pin "26") (pinfunction "PB6_26") (pintype "bidirectional"))
      (node (ref "U6") (pin "5") (pinfunction "RXD_5") (pintype "passive"))
    )
    (net (code "20") (name "/PA13") (class "Default")
      (node (ref "P1") (pin "3") (pinfunction "3_3") (pintype "passive"))
      (node (ref "U1") (pin "20") (pinfunction "PA13_20") (pintype "bidirectional"))
    )
    (net (code "21") (name "/RESET") (class "Default")
      (node (ref "C24") (pin "2") (pinfunction "2_2") (pintype "passive"))
      (node (ref "D1") (pin "1") (pinfunction "A_1") (pintype "passive"))
      (node (ref "R8") (pin "1") (pinfunction "1_1") (pintype "passive"))
      (node (ref "SW3") (pin "2") (pinfunction "2_2") (pintype "passive"))
      (node (ref "U1") (pin "5") (pinfunction "PF2-NRST_5") (pintype "bidirectional"))
    )
    (net (code "22") (name "/RF_CE") (class "Default")
      (node (ref "BK1") (pin "3") (pinfunction "CE_3") (pintype "passive"))
      (node (ref "R15") (pin "2") (pinfunction "2_2") (pintype "passive"))
      (node (ref "U1") (pin "28") (pinfunction "PB8_28") (pintype "bidirectional"))
      (node (ref "U3") (pin "3") (pinfunction "EN_3") (pintype "passive"))
    )
    (net (code "23") (name "/RTS") (class "Default")
      (node (ref "Q2") (pin "2") (pinfunction "E_2") (pintype "passive"))
      (node (ref "R11") (pin "1") (pinfunction "1_1") (pintype "passive"))
      (node (ref "U6") (pin "13") (pinfunction "RTS_13") (pintype "passive"))
    )
    (net (code "24") (name "/SCK") (class "Default")
      (node (ref "BK1") (pin "21") (pinfunction "SCK_21") (pintype "passive"))
      (node (ref "IC2") (pin "6") (pinfunction "SCL_6") (pintype "input"))
      (node (ref "JP3") (pin "3") (pinfunction "3_3") (pintype "passive"))
      (node (ref "R3") (pin "2") (pinfunction "2_2") (pintype "passive"))
      (node (ref "U1") (pin "18") (pinfunction "PA11[PA9]_18") (pintype "bidirectional"))
    )
    (net (code "25") (name "/SDA") (class "Default")
      (node (ref "BK1") (pin "22") (pinfunction "SDA_22") (pintype "passive"))
      (node (ref "IC2") (pin "5") (pinfunction "SDA_5") (pintype "bidirectional"))
      (node (ref "JP3") (pin "4") (pinfunction "4_4") (pintype "passive"))
      (node (ref "R1") (pin "2") (pinfunction "2_2") (pintype "passive"))
      (node (ref "U1") (pin "19") (pinfunction "PA12[PA10]_19") (pintype "bidirectional"))
    )
    (net (code "26") (name "/SYNC") (class "Default")
      (node (ref "R20") (pin "1") (pinfunction "1_1") (pintype "passive"))
      (node (ref "U1") (pin "16") (pinfunction "PA8_16") (pintype "bidirectional"))
    )
    (net (code "27") (name "/UD_N") (class "Default")
      (node (ref "U2") (pin "11") (pinfunction "DMU_11") (pintype "passive"))
      (node (ref "U8") (pin "3") (pinfunction "IO2_3") (pintype "passive"))
      (node (ref "USBC1") (pin "A7") (pinfunction "DN1_A7") (pintype "passive"))
      (node (ref "USBC1") (pin "B7") (pinfunction "DN2_B7") (pintype "passive"))
    )
    (net (code "28") (name "/UD_P") (class "Default")
      (node (ref "U2") (pin "12") (pinfunction "DPU_12") (pintype "passive"))
      (node (ref "U8") (pin "4") (pinfunction "IO3_4") (pintype "passive"))
      (node (ref "USBC1") (pin "A6") (pinfunction "DP1_A6") (pintype "passive"))
      (node (ref "USBC1") (pin "B6") (pinfunction "DP2_B6") (pintype "passive"))
    )
    (net (code "29") (name "/pcm_lrck") (class "Default")
      (node (ref "BK1") (pin "18") (pinfunction "GOPIO0_18") (pintype "passive"))
      (node (ref "U5") (pin "12") (pinfunction "MUTER_12") (pintype "passive"))
    )
    (net (code "30") (name "/pcm_sck") (class "Default")
      (node (ref "BK1") (pin "19") (pinfunction "GPIO1_19") (pintype "passive"))
      (node (ref "U5") (pin "11") (pinfunction "MUTEP_11") (pintype "passive"))
    )
    (net (code "31") (name "/pcm_sda") (class "Default")
      (node (ref "BK1") (pin "26") (pinfunction "GPIO3_26") (pintype "passive"))
      (node (ref "U5") (pin "14") (pinfunction "VOLUP_14") (pintype "passive"))
    )
    (net (code "32") (name "3V3") (class "Default")
      (node (ref "C11") (pin "2") (pinfunction "2_2") (pintype "passive"))
      (node (ref "C12") (pin "1") (pinfunction "1_1") (pintype "passive"))
      (node (ref "C13") (pin "1") (pinfunction "1_1") (pintype "passive"))
      (node (ref "C38") (pin "2") (pinfunction "2_2") (pintype "passive"))
      (node (ref "C40") (pin "1") (pinfunction "1_1") (pintype "passive"))
      (node (ref "C41") (pin "1") (pinfunction "1_1") (pintype "passive"))
      (node (ref "C42") (pin "2") (pinfunction "2_2") (pintype "passive"))
      (node (ref "C46") (pin "1") (pinfunction "1_1") (pintype "passive"))
      (node (ref "C49") (pin "1") (pinfunction "1_1") (pintype "passive"))
      (node (ref "C51") (pin "1") (pinfunction "1_1") (pintype "passive"))
      (node (ref "C54") (pin "1") (pinfunction "1_1") (pintype "passive"))
      (node (ref "C56") (pin "2") (pinfunction "2_2") (pintype "passive"))
      (node (ref "C62") (pin "2") (pinfunction "2_2") (pintype "passive"))
      (node (ref "C65") (pin "1") (pinfunction "1_1") (pintype "passive"))
      (node (ref "FB8") (pin "2") (pinfunction "2_2") (pintype "passive"))
      (node (ref "IC1") (pin "8") (pinfunction "VCC_8") (pintype "power_in"))
      (node (ref "IC2") (pin "8") (pinfunction "VCC_8") (pintype "power_in"))
      (node (ref "JP3") (pin "2") (pinfunction "2_2") (pintype "passive"))
      (node (ref "L3") (pin "2") (pinfunction "2_2") (pintype "passive"))
      (node (ref "Q3") (pin "2") (pinfunction "E_2") (pintype "passive"))
      (node (ref "R1") (pin "1") (pinfunction "1_1") (pintype "passive"))
      (node (ref "R13") (pin "2") (pinfunction "2_2") (pintype "passive"))
      (node (ref "R2") (pin "2") (pinfunction "2_2") (pintype "passive"))
      (node (ref "R23") (pin "2") (pinfunction "2_2") (pintype "passive"))
      (node (ref "R24") (pin "2") (pinfunction "2_2") (pintype "passive"))
      (node (ref "R3") (pin "1") (pinfunction "1_1") (pintype "passive"))
      (node (ref "R5") (pin "2") (pinfunction "2_2") (pintype "passive"))
      (node (ref "R8") (pin "2") (pinfunction "2_2") (pintype "passive"))
      (node (ref "R9") (pin "1") (pinfunction "1_1") (pintype "passive"))
      (node (ref "U1") (pin "3") (pinfunction "VDD_3") (pintype "power_in"))
      (node (ref "U2") (pin "16") (pinfunction "VDD33_16") (pintype "passive"))
      (node (ref "U6") (pin "1") (pinfunction "VIO_1") (pintype "passive"))
      (node (ref "U6") (pin "3") (pinfunction "VDD5_3") (pintype "passive"))
      (node (ref "U8") (pin "5") (pinfunction "VCC_5") (pintype "passive"))
      (node (ref "UWB1") (pin "5") (pinfunction "VDDAON_5") (pintype "passive"))
      (node (ref "UWB1") (pin "6") (pinfunction "VDD3V3_6") (pintype "passive"))
      (node (ref "UWB1") (pin "7") (pinfunction "VDD3V3_7") (pintype "passive"))
    )
    (net (code "33") (name "GND") (class "Default")
      (node (ref "C1") (pin "1") (pinfunction "1_1") (pintype "passive"))
      (node (ref "C11") (pin "1") (pinfunction "1_1") (pintype "passive"))
      (node (ref "C12") (pin "2") (pinfunction "2_2") (pintype "passive"))
      (node (ref "C13") (pin "2") (pinfunction "2_2") (pintype "passive"))
      (node (ref "C24") (pin "1") (pinfunction "1_1") (pintype "passive"))
      (node (ref "C26") (pin "1") (pinfunction "1_1") (pintype "passive"))
      (node (ref "C27") (pin "1") (pinfunction "1_1") (pintype "passive"))
      (node (ref "C28") (pin "1") (pinfunction "1_1") (pintype "passive"))
      (node (ref "C29") (pin "1") (pinfunction "1_1") (pintype "passive"))
      (node (ref "C30") (pin "1") (pinfunction "1_1") (pintype "passive"))
      (node (ref "C38") (pin "1") (pinfunction "1_1") (pintype "passive"))
      (node (ref "C39") (pin "1") (pinfunction "1_1") (pintype "passive"))
      (node (ref "C4") (pin "1") (pinfunction "1_1") (pintype "passive"))
      (node (ref "C40") (pin "2") (pinfunction "2_2") (pintype "passive"))
      (node (ref "C41") (pin "2") (pinfunction "2_2") (pintype "passive"))
      (node (ref "C42") (pin "1") (pinfunction "1_1") (pintype "passive"))
      (node (ref "C43") (pin "2") (pinfunction "2_2") (pintype "passive"))
      (node (ref "C47") (pin "2") (pinfunction "2_2") (pintype "passive"))
      (node (ref "C49") (pin "2") (pinfunction "2_2") (pintype "passive"))
      (node (ref "C50") (pin "1") (pinfunction "1_1") (pintype "passive"))
      (node (ref "C51") (pin "2") (pinfunction "2_2") (pintype "passive"))
      (node (ref "C53") (pin "1") (pinfunction "1_1") (pintype "passive"))
      (node (ref "C54") (pin "2") (pinfunction "2_2") (pintype "passive"))
      (node (ref "C56") (pin "1") (pinfunction "1_1") (pintype "passive"))
      (node (ref "C59") (pin "1") (pinfunction "1_1") (pintype "passive"))
      (node (ref "C62") (pin "1") (pinfunction "1_1") (pintype "passive"))
      (node (ref "C65") (pin "2") (pinfunction "2_2") (pintype "passive"))
      (node (ref "C66") (pin "1") (pinfunction "1_1") (pintype "passive"))
      (node (ref "FB5") (pin "1") (pinfunction "1_1") (pintype "passive"))
      (node (ref "FB7") (pin "1") (pinfunction "1_1") (pintype "passive"))
      (node (ref "IC1") (pin "1") (pinfunction "A0_1") (pintype "input"))
      (node (ref "IC1") (pin "2") (pinfunction "A1_2") (pintype "input"))
      (node (ref "IC1") (pin "3") (pinfunction "A2_3") (pintype "input"))
      (node (ref "IC1") (pin "4") (pinfunction "GND_4") (pintype "passive"))
      (node (ref "IC2") (pin "1") (pinfunction "A0_1") (pintype "input"))
      (node (ref "IC2") (pin "2") (pinfunction "A1_2") (pintype "input"))
      (node (ref "IC2") (pin "3") (pinfunction "A2_3") (pintype "input"))
      (node (ref "IC2") (pin "4") (pinfunction "GND_4") (pintype "passive"))
      (node (ref "JP3") (pin "1") (pinfunction "1_1") (pintype "passive"))
      (node (ref "LED4") (pin "2") (pinfunction "K_2") (pintype "passive"))
      (node (ref "P1") (pin "1") (pinfunction "1_1") (pintype "passive"))
      (node (ref "R14") (pin "1") (pinfunction "1_1") (pintype "passive"))
      (node (ref "R16") (pin "2") (pinfunction "2_2") (pintype "passive"))
      (node (ref "R17") (pin "2") (pinfunction "2_2") (pintype "passive"))
      (node (ref "R18") (pin "2") (pinfunction "2_2") (pintype "passive"))
      (node (ref "R19") (pin "1") (pinfunction "1_1") (pintype "passive"))
      (node (ref "R6") (pin "2") (pinfunction "2_2") (pintype "passive"))
      (node (ref "R7") (pin "2") (pinfunction "2_2") (pintype "passive"))
      (node (ref "SW1") (pin "2") (pinfunction "2_2") (pintype "passive"))
      (node (ref "SW2") (pin "2") (pinfunction "2_2") (pintype "passive"))
      (node (ref "SW3") (pin "1") (pinfunction "1_1") (pintype "passive"))
      (node (ref "U1") (pin "4") (pinfunction "VSS_4") (pintype "power_in"))
      (node (ref "U2") (pin "0") (pinfunction "GND_0") (pintype "passive"))
      (node (ref "U4") (pin "2") (pinfunction "GND_2") (pintype "passive"))
      (node (ref "U5") (pin "3") (pinfunction "VSSA_3") (pintype "passive"))
      (node (ref "U6") (pin "0") (pinfunction "GND_0") (pintype "passive"))
      (node (ref "U6") (pin "2") (pinfunction "GND_2") (pintype "passive"))
      (node (ref "U8") (pin "2") (pinfunction "GND_2") (pintype "passive"))
      (node (ref "USBC1") (pin "0") (pinfunction "0_0") (pintype "passive"))
      (node (ref "USBC1") (pin "A1") (pinfunction "GND_A1") (pintype "passive"))
      (node (ref "USBC1") (pin "A12") (pinfunction "GND_A12") (pintype "passive"))
      (node (ref "USBC1") (pin "B1") (pinfunction "GND_B1") (pintype "passive"))
      (node (ref "USBC1") (pin "B12") (pinfunction "GND_B12") (pintype "passive"))
      (node (ref "UWB1") (pin "16") (pinfunction "VSS_16") (pintype "passive"))
      (node (ref "UWB1") (pin "21") (pinfunction "VSS_21") (pintype "passive"))
      (node (ref "UWB1") (pin "23") (pinfunction "VSS_23") (pintype "passive"))
      (node (ref "UWB1") (pin "24") (pinfunction "VSS_24") (pintype "passive"))
      (node (ref "UWB1") (pin "8") (pinfunction "VSS_8") (pintype "passive"))
      (node (ref "X1") (pin "2") (pinfunction "GND_2") (pintype "passive"))
      (node (ref "X2") (pin "2") (pinfunction "2_2") (pintype "passive"))
      (node (ref "X2") (pin "4") (pinfunction "4_4") (pintype "passive"))
    )
    (net (code "34") (name "GNDA") (class "Default")
      (node (ref "C44") (pin "1") (pinfunction "1_1") (pintype "passive"))
      (node (ref "C45") (pin "1") (pinfunction "1_1") (pintype "passive"))
      (node (ref "C52") (pin "1") (pinfunction "1_1") (pintype "passive"))
      (node (ref "C55") (pin "1") (pinfunction "1_1") (pintype "passive"))
      (node (ref "C57") (pin "1") (pinfunction "1_1") (pintype "passive"))
      (node (ref "C58") (pin "1") (pinfunction "1_1") (pintype "passive"))
      (node (ref "C67") (pin "1") (pinfunction "1_1") (pintype "passive"))
      (node (ref "C68") (pin "1") (pinfunction "1_1") (pintype "passive"))
      (node (ref "FB7") (pin "2") (pinfunction "2_2") (pintype "passive"))
      (node (ref "U5") (pin "27") (pinfunction "GND_HP_27") (pintype "passive"))
      (node (ref "U5") (pin "36") (pinfunction "AVSS_36") (pintype "passive"))
      (node (ref "U5") (pin "44") (pinfunction "GNDCP_44") (pintype "passive"))
    )
    (net (code "35") (name "GNDRF") (class "Default")
      (node (ref "BK1") (pin "33") (pinfunction "33_33") (pintype "passive"))
      (node (ref "C17") (pin "2") (pinfunction "2_2") (pintype "passive"))
      (node (ref "C18") (pin "2") (pinfunction "2_2") (pintype "passive"))
      (node (ref "C19") (pin "2") (pinfunction "2_2") (pintype "passive"))
      (node (ref "C2") (pin "1") (pinfunction "1_1") (pintype "passive"))
      (node (ref "C20") (pin "2") (pinfunction "2_2") (pintype "passive"))
      (node (ref "C21") (pin "2") (pinfunction "2_2") (pintype "passive"))
      (node (ref "C23") (pin "1") (pinfunction "1_1") (pintype "passive"))
      (node (ref "C25") (pin "2") (pinfunction "2_2") (pintype "passive"))
      (node (ref "C3") (pin "1") (pinfunction "1_1") (pintype "passive"))
      (node (ref "C31") (pin "1") (pinfunction "1_1") (pintype "passive"))
      (node (ref "C32") (pin "1") (pinfunction "1_1") (pintype "passive"))
      (node (ref "C33") (pin "1") (pinfunction "1_1") (pintype "passive"))
      (node (ref "C34") (pin "2") (pinfunction "2_2") (pintype "passive"))
      (node (ref "C35") (pin "2") (pinfunction "2_2") (pintype "passive"))
      (node (ref "C36") (pin "2") (pinfunction "2_2") (pintype "passive"))
      (node (ref "C37") (pin "1") (pinfunction "1_1") (pintype "passive"))
      (node (ref "C5") (pin "1") (pinfunction "1_1") (pintype "passive"))
      (node (ref "C6") (pin "1") (pinfunction "1_1") (pintype "passive"))
      (node (ref "C7") (pin "1") (pinfunction "1_1") (pintype "passive"))
      (node (ref "C8") (pin "1") (pinfunction "1_1") (pintype "passive"))
      (node (ref "FB5") (pin "2") (pinfunction "2_2") (pintype "passive"))
      (node (ref "JP1") (pin "2") (pinfunction "GND_2") (pintype "passive"))
      (node (ref "JP1") (pin "3") (pinfunction "GND_3") (pintype "passive"))
      (node (ref "JP2") (pin "2") (pinfunction "GND_2") (pintype "passive"))
      (node (ref "JP2") (pin "3") (pinfunction "GND_3") (pintype "passive"))
      (node (ref "L5") (pin "1") (pinfunction "1_1") (pintype "passive"))
      (node (ref "R15") (pin "1") (pinfunction "1_1") (pintype "passive"))
      (node (ref "U3") (pin "2") (pinfunction "GND_2") (pintype "passive"))
    )
    (net (code "36") (name "Net-(BK1-EXCN)") (class "Default")
      (node (ref "BK1") (pin "12") (pinfunction "EXCN_12") (pintype "passive"))
      (node (ref "C22") (pin "2") (pinfunction "2_2") (pintype "passive"))
    )
    (net (code "37") (name "Net-(BK1-EXCP)") (class "Default")
      (node (ref "BK1") (pin "11") (pinfunction "EXCP_11") (pintype "passive"))
      (node (ref "C22") (pin "1") (pinfunction "1_1") (pintype "passive"))
    )
    (net (code "38") (name "Net-(BK1-TXON)") (class "Default")
      (node (ref "BK1") (pin "9") (pinfunction "TXON_9") (pintype "passive"))
      (node (ref "C10") (pin "1") (pinfunction "1_1") (pintype "passive"))
      (node (ref "L1") (pin "1") (pinfunction "1_1") (pintype "passive"))
    )
    (net (code "39") (name "Net-(BK1-TXOP)") (class "Default")
      (node (ref "BK1") (pin "10") (pinfunction "TXOP_10") (pintype "passive"))
      (node (ref "C16") (pin "1") (pinfunction "1_1") (pintype "passive"))
      (node (ref "L2") (pin "1") (pinfunction "1_1") (pintype "passive"))
    )
    (net (code "40") (name "Net-(BK1-VCCTX)") (class "Default")
      (node (ref "BK1") (pin "7") (pinfunction "VCCTX_7") (pintype "passive"))
      (node (ref "FB1") (pin "2") (pinfunction "2_2") (pintype "passive"))
    )
    (net (code "41") (name "Net-(BK1-VDDDIG)") (class "Default")
      (node (ref "BK1") (pin "17") (pinfunction "VDDDIG_17") (pintype "passive"))
      (node (ref "C32") (pin "2") (pinfunction "2_2") (pintype "passive"))
    )
    (net (code "42") (name "Net-(BK1-VDDVCO)") (class "Default")
      (node (ref "BK1") (pin "1") (pinfunction "VDDVCO_1") (pintype "passive"))
      (node (ref "C7") (pin "2") (pinfunction "2_2") (pintype "passive"))
    )
    (net (code "43") (name "Net-(BK1-XI)") (class "Default")
      (node (ref "BK1") (pin "31") (pinfunction "XI_31") (pintype "passive"))
      (node (ref "C20") (pin "1") (pinfunction "1_1") (pintype "passive"))
      (node (ref "X3") (pin "1") (pinfunction "1_1") (pintype "passive"))
    )
    (net (code "44") (name "Net-(BK1-XO)") (class "Default")
      (node (ref "BK1") (pin "30") (pinfunction "XO_30") (pintype "passive"))
      (node (ref "C21") (pin "1") (pinfunction "1_1") (pintype "passive"))
      (node (ref "X3") (pin "2") (pinfunction "2_2") (pintype "passive"))
    )
    (net (code "45") (name "Net-(C2-Pad2)") (class "Default")
      (node (ref "C2") (pin "2") (pinfunction "2_2") (pintype "passive"))
      (node (ref "C3") (pin "2") (pinfunction "2_2") (pintype "passive"))
      (node (ref "FB1") (pin "1") (pinfunction "1_1") (pintype "passive"))
      (node (ref "L1") (pin "2") (pinfunction "2_2") (pintype "passive"))
      (node (ref "L2") (pin "2") (pinfunction "2_2") (pintype "passive"))
    )
    (net (code "46") (name "Net-(C10-Pad2)") (class "Default")
      (node (ref "C10") (pin "2") (pinfunction "2_2") (pintype "passive"))
      (node (ref "C8") (pin "2") (pinfunction "2_2") (pintype "passive"))
      (node (ref "L4") (pin "2") (pinfunction "2_2") (pintype "passive"))
    )
    (net (code "47") (name "Net-(C15-Pad1)") (class "Default")
      (node (ref "C15") (pin "1") (pinfunction "1_1") (pintype "passive"))
      (node (ref "C16") (pin "2") (pinfunction "2_2") (pintype "passive"))
      (node (ref "L5") (pin "2") (pinfunction "2_2") (pintype "passive"))
    )
    (net (code "48") (name "Net-(C15-Pad2)") (class "Default")
      (node (ref "C15") (pin "2") (pinfunction "2_2") (pintype "passive"))
      (node (ref "C9") (pin "1") (pinfunction "1_1") (pintype "passive"))
      (node (ref "L4") (pin "1") (pinfunction "1_1") (pintype "passive"))
    )
    (net (code "49") (name "Net-(D1-K)") (class "Default")
      (node (ref "D1") (pin "2") (pinfunction "K_2") (pintype "passive"))
      (node (ref "Q2") (pin "3") (pinfunction "C_3") (pintype "passive"))
      (node (ref "R9") (pin "2") (pinfunction "2_2") (pintype "passive"))
    )
    (net (code "50") (name "Net-(IC1-SCL)") (class "Default")
      (node (ref "IC1") (pin "6") (pinfunction "SCL_6") (pintype "input"))
      (node (ref "R23") (pin "1") (pinfunction "1_1") (pintype "passive"))
      (node (ref "U5") (pin "18") (pinfunction "I2C_SCL_18") (pintype "passive"))
    )
    (net (code "51") (name "Net-(IC1-SDA)") (class "Default")
      (node (ref "IC1") (pin "5") (pinfunction "SDA_5") (pintype "bidirectional"))
      (node (ref "R24") (pin "1") (pinfunction "1_1") (pintype "passive"))
      (node (ref "U5") (pin "19") (pinfunction "I2C_SDA_19") (pintype "passive"))
    )
    (net (code "52") (name "Net-(JP1-ANT)") (class "Default")
      (node (ref "C18") (pin "1") (pinfunction "1_1") (pintype "passive"))
      (node (ref "C9") (pin "2") (pinfunction "2_2") (pintype "passive"))
      (node (ref "JP1") (pin "1") (pinfunction "ANT_1") (pintype "passive"))
      (node (ref "R25") (pin "1") (pinfunction "1_1") (pintype "passive"))
    )
    (net (code "53") (name "Net-(JP2-ANT)") (class "Default")
      (node (ref "C17") (pin "1") (pinfunction "1_1") (pintype "passive"))
      (node (ref "JP2") (pin "1") (pinfunction "ANT_1") (pintype "passive"))
      (node (ref "R25") (pin "2") (pinfunction "2_2") (pintype "passive"))
    )
    (net (code "54") (name "Net-(LED1-A)") (class "Default")
      (node (ref "LED1") (pin "1") (pinfunction "A_1") (pintype "passive"))
      (node (ref "R5") (pin "1") (pinfunction "1_1") (pintype "passive"))
    )
    (net (code "55") (name "Net-(LED2-A)") (class "Default")
      (node (ref "LED2") (pin "1") (pinfunction "A_1") (pintype "passive"))
      (node (ref "R2") (pin "1") (pinfunction "1_1") (pintype "passive"))
    )
    (net (code "56") (name "Net-(LED3-A)") (class "Default")
      (node (ref "LED3") (pin "1") (pinfunction "A_1") (pintype "passive"))
      (node (ref "UWB1") (pin "13") (pinfunction "GPIO2_13") (pintype "passive"))
    )
    (net (code "57") (name "Net-(LED3-K)") (class "Default")
      (node (ref "LED3") (pin "2") (pinfunction "K_2") (pintype "passive"))
      (node (ref "R7") (pin "1") (pinfunction "1_1") (pintype "passive"))
    )
    (net (code "58") (name "Net-(LED4-A)") (class "Default")
      (node (ref "LED4") (pin "1") (pinfunction "A_1") (pintype "passive"))
      (node (ref "R22") (pin "1") (pinfunction "1_1") (pintype "passive"))
    )
    (net (code "59") (name "Net-(LED5-A)") (class "Default")
      (node (ref "LED5") (pin "1") (pinfunction "A_1") (pintype "passive"))
      (node (ref "UWB1") (pin "12") (pinfunction "GPIO3_12") (pintype "passive"))
    )
    (net (code "60") (name "Net-(LED5-K)") (class "Default")
      (node (ref "LED5") (pin "2") (pinfunction "K_2") (pintype "passive"))
      (node (ref "R16") (pin "1") (pinfunction "1_1") (pintype "passive"))
    )
    (net (code "61") (name "Net-(Q2-B)") (class "Default")
      (node (ref "Q2") (pin "1") (pinfunction "B_1") (pintype "passive"))
      (node (ref "R10") (pin "2") (pinfunction "2_2") (pintype "passive"))
    )
    (net (code "62") (name "Net-(Q3-B)") (class "Default")
      (node (ref "Q3") (pin "1") (pinfunction "B_1") (pintype "passive"))
      (node (ref "R11") (pin "2") (pinfunction "2_2") (pintype "passive"))
    )
    (net (code "63") (name "Net-(Q3-C)") (class "Default")
      (node (ref "Q3") (pin "3") (pinfunction "C_3") (pintype "passive"))
      (node (ref "R12") (pin "1") (pinfunction "1_1") (pintype "passive"))
    )
    (net (code "64") (name "Net-(U1-PB3)") (class "Default")
      (node (ref "C1") (pin "2") (pinfunction "2_2") (pintype "passive"))
      (node (ref "SW1") (pin "1") (pinfunction "1_1") (pintype "passive"))
      (node (ref "U1") (pin "23") (pinfunction "PB3_23") (pintype "bidirectional"))
    )
    (net (code "65") (name "Net-(U1-PB4)") (class "Default")
      (node (ref "C4") (pin "2") (pinfunction "2_2") (pintype "passive"))
      (node (ref "SW2") (pin "1") (pinfunction "1_1") (pintype "passive"))
      (node (ref "U1") (pin "24") (pinfunction "PB4_24") (pintype "bidirectional"))
    )
    (net (code "66") (name "Net-(U1-PC14-OSC32_IN)") (class "Default")
      (node (ref "R4") (pin "1") (pinfunction "1_1") (pintype "passive"))
      (node (ref "U1") (pin "1") (pinfunction "PC14-OSC32_IN_1") (pintype "bidirectional"))
    )
    (net (code "67") (name "Net-(U2-XI)") (class "Default")
      (node (ref "U2") (pin "2") (pinfunction "XI_2") (pintype "passive"))
      (node (ref "X2") (pin "3") (pinfunction "3_3") (pintype "passive"))
    )
    (net (code "68") (name "Net-(U2-XO)") (class "Default")
      (node (ref "U2") (pin "1") (pinfunction "XO_1") (pintype "passive"))
      (node (ref "X2") (pin "1") (pinfunction "1_1") (pintype "passive"))
    )
    (net (code "69") (name "Net-(U4-FB)") (class "Default")
      (node (ref "C46") (pin "2") (pinfunction "2_2") (pintype "passive"))
      (node (ref "R13") (pin "1") (pinfunction "1_1") (pintype "passive"))
      (node (ref "R14") (pin "2") (pinfunction "2_2") (pintype "passive"))
      (node (ref "U4") (pin "5") (pinfunction "FB_5") (pintype "passive"))
    )
    (net (code "70") (name "Net-(U4-LX)") (class "Default")
      (node (ref "L3") (pin "1") (pinfunction "1_1") (pintype "passive"))
      (node (ref "U4") (pin "3") (pinfunction "LX_3") (pintype "passive"))
    )
    (net (code "71") (name "Net-(U5-CFLYN)") (class "Default")
      (node (ref "C48") (pin "1") (pinfunction "1_1") (pintype "passive"))
      (node (ref "U5") (pin "43") (pinfunction "CFLYN_43") (pintype "passive"))
    )
    (net (code "72") (name "Net-(U5-CFLYP)") (class "Default")
      (node (ref "C48") (pin "2") (pinfunction "2_2") (pintype "passive"))
      (node (ref "U5") (pin "45") (pinfunction "CFLYP_45") (pintype "passive"))
    )
    (net (code "73") (name "Net-(U5-HPVDD)") (class "Default")
      (node (ref "C55") (pin "2") (pinfunction "2_2") (pintype "passive"))
      (node (ref "U5") (pin "40") (pinfunction "HPVDD_40") (pintype "passive"))
      (node (ref "U5") (pin "41") (pinfunction "VCPP_41") (pintype "passive"))
    )
    (net (code "74") (name "Net-(U5-HPVSS)") (class "Default")
      (node (ref "C52") (pin "2") (pinfunction "2_2") (pintype "passive"))
      (node (ref "U5") (pin "37") (pinfunction "HPVSS_37") (pintype "passive"))
      (node (ref "U5") (pin "42") (pinfunction "VCPN_42") (pintype "passive"))
    )
    (net (code "75") (name "Net-(U5-LEDO)") (class "Default")
      (node (ref "R22") (pin "2") (pinfunction "2_2") (pintype "passive"))
      (node (ref "U5") (pin "8") (pinfunction "LEDO_8") (pintype "passive"))
    )
    (net (code "76") (name "Net-(U5-TEST)") (class "Default")
      (node (ref "R18") (pin "1") (pinfunction "1_1") (pintype "passive"))
      (node (ref "U5") (pin "47") (pinfunction "TEST_47") (pintype "passive"))
    )
    (net (code "77") (name "Net-(U5-V12)") (class "Default")
      (node (ref "C53") (pin "2") (pinfunction "2_2") (pintype "passive"))
      (node (ref "U5") (pin "4") (pinfunction "V12_4") (pintype "passive"))
    )
    (net (code "78") (name "Net-(U5-VMID)") (class "Default")
      (node (ref "C57") (pin "2") (pinfunction "2_2") (pintype "passive"))
      (node (ref "C58") (pin "2") (pinfunction "2_2") (pintype "passive"))
      (node (ref "U5") (pin "35") (pinfunction "VMID_35") (pintype "passive"))
    )
    (net (code "79") (name "Net-(U6-V3)") (class "Default")
      (node (ref "C59") (pin "2") (pinfunction "2_2") (pintype "passive"))
      (node (ref "U6") (pin "6") (pinfunction "V3_6") (pintype "passive"))
    )
    (net (code "80") (name "Net-(USBC1-CC1)") (class "Default")
      (node (ref "R19") (pin "2") (pinfunction "2_2") (pintype "passive"))
      (node (ref "USBC1") (pin "A5") (pinfunction "CC1_A5") (pintype "passive"))
    )
    (net (code "81") (name "Net-(USBC1-CC2)") (class "Default")
      (node (ref "R17") (pin "1") (pinfunction "1_1") (pintype "passive"))
      (node (ref "USBC1") (pin "B5") (pinfunction "CC2_B5") (pintype "passive"))
    )
    (net (code "82") (name "Net-(UWB1-SYNC)") (class "Default")
      (node (ref "R20") (pin "2") (pinfunction "2_2") (pintype "passive"))
      (node (ref "UWB1") (pin "4") (pinfunction "SYNC_4") (pintype "passive"))
    )
    (net (code "83") (name "Net-(X1-OUT)") (class "Default")
      (node (ref "R4") (pin "2") (pinfunction "2_2") (pintype "passive"))
      (node (ref "X1") (pin "3") (pinfunction "OUT_3") (pintype "passive"))
    )
    (net (code "84") (name "Net-(X1-VCC)") (class "Default")
      (node (ref "C26") (pin "2") (pinfunction "2_2") (pintype "passive"))
      (node (ref "C30") (pin "2") (pinfunction "2_2") (pintype "passive"))
      (node (ref "FB8") (pin "1") (pinfunction "1_1") (pintype "passive"))
      (node (ref "X1") (pin "4") (pinfunction "VCC_4") (pintype "passive"))
    )
    (net (code "85") (name "RF3V3") (class "Default")
      (node (ref "BK1") (pin "13") (pinfunction "VCCAUD_13") (pintype "passive"))
      (node (ref "BK1") (pin "16") (pinfunction "VCCDIG_16") (pintype "passive"))
      (node (ref "BK1") (pin "2") (pinfunction "VCCVCO_2") (pintype "passive"))
      (node (ref "BK1") (pin "24") (pinfunction "VCCIF_24") (pintype "passive"))
      (node (ref "BK1") (pin "28") (pinfunction "VCCDVCO_28") (pintype "passive"))
      (node (ref "BK1") (pin "29") (pinfunction "VCCXTAL_29") (pintype "passive"))
      (node (ref "BK1") (pin "32") (pinfunction "VCCPLL_32") (pintype "passive"))
      (node (ref "BK1") (pin "4") (pinfunction "VCCB_4") (pintype "passive"))
      (node (ref "BK1") (pin "8") (pinfunction "VCCPA_8") (pintype "passive"))
      (node (ref "C19") (pin "1") (pinfunction "1_1") (pintype "passive"))
      (node (ref "C23") (pin "2") (pinfunction "2_2") (pintype "passive"))
      (node (ref "C25") (pin "1") (pinfunction "1_1") (pintype "passive"))
      (node (ref "C31") (pin "2") (pinfunction "2_2") (pintype "passive"))
      (node (ref "C33") (pin "2") (pinfunction "2_2") (pintype "passive"))
      (node (ref "C35") (pin "1") (pinfunction "1_1") (pintype "passive"))
      (node (ref "C36") (pin "1") (pinfunction "1_1") (pintype "passive"))
      (node (ref "C37") (pin "2") (pinfunction "2_2") (pintype "passive"))
      (node (ref "C5") (pin "2") (pinfunction "2_2") (pintype "passive"))
      (node (ref "C6") (pin "2") (pinfunction "2_2") (pintype "passive"))
      (node (ref "U3") (pin "5") (pinfunction "VOUT_5") (pintype "passive"))
    )
    (net (code "86") (name "USB_5V") (class "Default")
      (node (ref "C27") (pin "2") (pinfunction "2_2") (pintype "passive"))
      (node (ref "C34") (pin "1") (pinfunction "1_1") (pintype "passive"))
      (node (ref "C39") (pin "2") (pinfunction "2_2") (pintype "passive"))
      (node (ref "C43") (pin "1") (pinfunction "1_1") (pintype "passive"))
      (node (ref "C47") (pin "1") (pinfunction "1_1") (pintype "passive"))
      (node (ref "FB4") (pin "1") (pinfunction "1_1") (pintype "passive"))
      (node (ref "U2") (pin "15") (pinfunction "V5_15") (pintype "passive"))
      (node (ref "U3") (pin "1") (pinfunction "VIN_1") (pintype "passive"))
      (node (ref "U4") (pin "1") (pinfunction "EN_1") (pintype "passive"))
      (node (ref "U4") (pin "4") (pinfunction "VIN_4") (pintype "passive"))
      (node (ref "U5") (pin "1") (pinfunction "VBUS_1") (pintype "passive"))
      (node (ref "U6") (pin "9") (pinfunction "VBUS_9") (pintype "passive"))
    )
    (net (code "87") (name "VBUS") (class "Default")
      (node (ref "C28") (pin "2") (pinfunction "2_2") (pintype "passive"))
      (node (ref "C29") (pin "2") (pinfunction "2_2") (pintype "passive"))
      (node (ref "FB4") (pin "2") (pinfunction "2_2") (pintype "passive"))
      (node (ref "USBC1") (pin "A4") (pinfunction "VBUS_A4") (pintype "passive"))
      (node (ref "USBC1") (pin "A9") (pinfunction "VBUS_A9") (pintype "passive"))
      (node (ref "USBC1") (pin "B4") (pinfunction "VBUS_B4") (pintype "passive"))
      (node (ref "USBC1") (pin "B9") (pinfunction "VBUS_B9") (pintype "passive"))
    )
    (net (code "88") (name "unconnected-(BK1-GPIO2-Pad20)") (class "Default")
      (node (ref "BK1") (pin "20") (pinfunction "GPIO2_20") (pintype "passive"))
    )
    (net (code "89") (name "unconnected-(BK1-GPIO4-Pad25)") (class "Default")
      (node (ref "BK1") (pin "25") (pinfunction "GPIO4_25") (pintype "passive+no_connect"))
    )
    (net (code "90") (name "unconnected-(BK1-IRQ-Pad27)") (class "Default")
      (node (ref "BK1") (pin "27") (pinfunction "IRQ_27") (pintype "passive+no_connect"))
    )
    (net (code "91") (name "unconnected-(BK1-MICN-Pad14)") (class "Default")
      (node (ref "BK1") (pin "14") (pinfunction "MICN_14") (pintype "passive+no_connect"))
    )
    (net (code "92") (name "unconnected-(BK1-MICP-Pad15)") (class "Default")
      (node (ref "BK1") (pin "15") (pinfunction "MICP_15") (pintype "passive+no_connect"))
    )
    (net (code "93") (name "unconnected-(BK1-NC-Pad5)") (class "Default")
      (node (ref "BK1") (pin "5") (pinfunction "NC_5") (pintype "passive"))
    )
    (net (code "94") (name "unconnected-(BK1-NC-Pad6)") (class "Default")
      (node (ref "BK1") (pin "6") (pinfunction "NC_6") (pintype "passive"))
    )
    (net (code "95") (name "unconnected-(BK1-XO2-Pad23)") (class "Default")
      (node (ref "BK1") (pin "23") (pinfunction "XO2_23") (pintype "passive"))
    )
    (net (code "96") (name "unconnected-(IC1-WP-Pad7)") (class "Default")
      (node (ref "IC1") (pin "7") (pinfunction "WP_7") (pintype "passive+no_connect"))
    )
    (net (code "97") (name "unconnected-(IC2-WP-Pad7)") (class "Default")
      (node (ref "IC2") (pin "7") (pinfunction "WP_7") (pintype "passive+no_connect"))
    )
    (net (code "98") (name "unconnected-(U1-PA4-Pad10)") (class "Default")
      (node (ref "U1") (pin "10") (pinfunction "PA4_10") (pintype "bidirectional+no_connect"))
    )
    (net (code "99") (name "unconnected-(U1-PA15-Pad22)") (class "Default")
      (node (ref "U1") (pin "22") (pinfunction "PA15_22") (pintype "bidirectional"))
    )
    (net (code "100") (name "unconnected-(U1-PB1-Pad15)") (class "Default")
      (node (ref "U1") (pin "15") (pinfunction "PB1_15") (pintype "bidirectional+no_connect"))
    )
    (net (code "101") (name "unconnected-(U1-PB5-Pad25)") (class "Default")
      (node (ref "U1") (pin "25") (pinfunction "PB5_25") (pintype "bidirectional+no_connect"))
    )
    (net (code "102") (name "unconnected-(U1-PC6-Pad17)") (class "Default")
      (node (ref "U1") (pin "17") (pinfunction "PC6_17") (pintype "bidirectional+no_connect"))
    )
    (net (code "103") (name "unconnected-(U2-DM1-Pad9)") (class "Default")
      (node (ref "U2") (pin "9") (pinfunction "DM1_9") (pintype "passive+no_connect"))
    )
    (net (code "104") (name "unconnected-(U2-DM3-Pad5)") (class "Default")
      (node (ref "U2") (pin "5") (pinfunction "DM3_5") (pintype "passive+no_connect"))
    )
    (net (code "105") (name "unconnected-(U2-DP1-Pad10)") (class "Default")
      (node (ref "U2") (pin "10") (pinfunction "DP1_10") (pintype "passive+no_connect"))
    )
    (net (code "106") (name "unconnected-(U2-DP3-Pad6)") (class "Default")
      (node (ref "U2") (pin "6") (pinfunction "DP3_6") (pintype "passive+no_connect"))
    )
    (net (code "107") (name "unconnected-(U2-PGANG-Pad14)") (class "Default")
      (node (ref "U2") (pin "14") (pinfunction "PGANG_14") (pintype "passive+no_connect"))
    )
    (net (code "108") (name "unconnected-(U2-~{RESET}{slash}CDP-Pad13)") (class "Default")
      (node (ref "U2") (pin "13") (pinfunction "~{RESET}/CDP_13") (pintype "passive+no_connect"))
    )
    (net (code "109") (name "unconnected-(U3-NC-Pad4)") (class "Default")
      (node (ref "U3") (pin "4") (pinfunction "NC_4") (pintype "passive+no_connect"))
    )
    (net (code "110") (name "unconnected-(U5-EQ3D_LED-Pad48)") (class "Default")
      (node (ref "U5") (pin "48") (pinfunction "EQ3D_LED_48") (pintype "passive+no_connect"))
    )
    (net (code "111") (name "unconnected-(U5-INSEL-Pad9)") (class "Default")
      (node (ref "U5") (pin "9") (pinfunction "INSEL_9") (pintype "passive+no_connect"))
    )
    (net (code "112") (name "unconnected-(U5-KEY_RENC_INV-Pad7)") (class "Default")
      (node (ref "U5") (pin "7") (pinfunction "KEY_RENC_INV_7") (pintype "passive+no_connect"))
    )
    (net (code "113") (name "unconnected-(U5-LHPOUT-Pad39)") (class "Default")
      (node (ref "U5") (pin "39") (pinfunction "LHPOUT_39") (pintype "passive+no_connect"))
    )
    (net (code "114") (name "unconnected-(U5-MIC1-Pad29)") (class "Default")
      (node (ref "U5") (pin "29") (pinfunction "MIC1_29") (pintype "passive+no_connect"))
    )
    (net (code "115") (name "unconnected-(U5-MIC1N-Pad31)") (class "Default")
      (node (ref "U5") (pin "31") (pinfunction "MIC1N_31") (pintype "passive+no_connect"))
    )
    (net (code "116") (name "unconnected-(U5-MIC1P-Pad32)") (class "Default")
      (node (ref "U5") (pin "32") (pinfunction "MIC1P_32") (pintype "passive+no_connect"))
    )
    (net (code "117") (name "unconnected-(U5-MIC2P-Pad33)") (class "Default")
      (node (ref "U5") (pin "33") (pinfunction "MIC2P_33") (pintype "passive+no_connect"))
    )
    (net (code "118") (name "unconnected-(U5-MICBIAS-Pad30)") (class "Default")
      (node (ref "U5") (pin "30") (pinfunction "MICBIAS_30") (pintype "passive+no_connect"))
    )
    (net (code "119") (name "unconnected-(U5-MSEL-Pad10)") (class "Default")
      (node (ref "U5") (pin "10") (pinfunction "MSEL_10") (pintype "passive+no_connect"))
    )
    (net (code "120") (name "unconnected-(U5-NEXT_TRACK-Pad20)") (class "Default")
      (node (ref "U5") (pin "20") (pinfunction "NEXT_TRACK_20") (pintype "passive+no_connect"))
    )
    (net (code "121") (name "unconnected-(U5-PALY_PAUSE-Pad22)") (class "Default")
      (node (ref "U5") (pin "22") (pinfunction "PALY_PAUSE_22") (pintype "passive+no_connect"))
    )
    (net (code "122") (name "unconnected-(U5-PLAY_EN-Pad16)") (class "Default")
      (node (ref "U5") (pin "16") (pinfunction "PLAY_EN_16") (pintype "passive+no_connect"))
    )
    (net (code "123") (name "unconnected-(U5-PRE_TACK-Pad21)") (class "Default")
      (node (ref "U5") (pin "21") (pinfunction "PRE_TACK_21") (pintype "passive+no_connect"))
    )
    (net (code "124") (name "unconnected-(U5-REC_EN-Pad17)") (class "Default")
      (node (ref "U5") (pin "17") (pinfunction "REC_EN_17") (pintype "passive+no_connect"))
    )
    (net (code "125") (name "unconnected-(U5-RHPOUT-Pad38)") (class "Default")
      (node (ref "U5") (pin "38") (pinfunction "RHPOUT_38") (pintype "passive+no_connect"))
    )
    (net (code "126") (name "unconnected-(U5-RING2-Pad28)") (class "Default")
      (node (ref "U5") (pin "28") (pinfunction "RING2_28") (pintype "passive+no_connect"))
    )
    (net (code "127") (name "unconnected-(U5-SLEEVE-Pad26)") (class "Default")
      (node (ref "U5") (pin "26") (pinfunction "SLEEVE_26") (pintype "passive+no_connect"))
    )
    (net (code "128") (name "unconnected-(U5-STEREO_MIC-Pad13)") (class "Default")
      (node (ref "U5") (pin "13") (pinfunction "STEREO_MIC_13") (pintype "passive+no_connect"))
    )
    (net (code "129") (name "unconnected-(U5-STOP-Pad24)") (class "Default")
      (node (ref "U5") (pin "24") (pinfunction "STOP_24") (pintype "passive+no_connect"))
    )
    (net (code "130") (name "unconnected-(U5-VOLDN-Pad15)") (class "Default")
      (node (ref "U5") (pin "15") (pinfunction "VOLDN_15") (pintype "passive+no_connect"))
    )
    (net (code "131") (name "unconnected-(U5-VP_MUTE-Pad25)") (class "Default")
      (node (ref "U5") (pin "25") (pinfunction "VP_MUTE_25") (pintype "passive+no_connect"))
    )
    (net (code "132") (name "unconnected-(U5-VR_MUTE-Pad23)") (class "Default")
      (node (ref "U5") (pin "23") (pinfunction "VR_MUTE_23") (pintype "passive+no_connect"))
    )
    (net (code "133") (name "unconnected-(U6-CTS-Pad15)") (class "Default")
      (node (ref "U6") (pin "15") (pinfunction "CTS_15") (pintype "passive+no_connect"))
    )
    (net (code "134") (name "unconnected-(U6-DCD-Pad11)") (class "Default")
      (node (ref "U6") (pin "11") (pinfunction "DCD_11") (pintype "passive+no_connect"))
    )
    (net (code "135") (name "unconnected-(U6-DSR-Pad14)") (class "Default")
      (node (ref "U6") (pin "14") (pinfunction "DSR_14") (pintype "passive+no_connect"))
    )
    (net (code "136") (name "unconnected-(U6-RI-Pad16)") (class "Default")
      (node (ref "U6") (pin "16") (pinfunction "RI_16") (pintype "passive+no_connect"))
    )
    (net (code "137") (name "unconnected-(U6-~{ACT}-Pad10)") (class "Default")
      (node (ref "U6") (pin "10") (pinfunction "~{ACT}_10") (pintype "passive+no_connect"))
    )
    (net (code "138") (name "unconnected-(U8-IO1-Pad1)") (class "Default")
      (node (ref "U8") (pin "1") (pinfunction "IO1_1") (pintype "passive+no_connect"))
    )
    (net (code "139") (name "unconnected-(U8-IO4-Pad6)") (class "Default")
      (node (ref "U8") (pin "6") (pinfunction "IO4_6") (pintype "passive+no_connect"))
    )
    (net (code "140") (name "unconnected-(USBC1-SBU1-PadA8)") (class "Default")
      (node (ref "USBC1") (pin "A8") (pinfunction "SBU1_A8") (pintype "passive"))
    )
    (net (code "141") (name "unconnected-(USBC1-SBU2-PadB8)") (class "Default")
      (node (ref "USBC1") (pin "B8") (pinfunction "SBU2_B8") (pintype "passive"))
    )
    (net (code "142") (name "unconnected-(UWB1-EXTON-Pad1)") (class "Default")
      (node (ref "UWB1") (pin "1") (pinfunction "EXTON_1") (pintype "passive+no_connect"))
    )
    (net (code "143") (name "unconnected-(UWB1-GPIO0-Pad15)") (class "Default")
      (node (ref "UWB1") (pin "15") (pinfunction "GPIO0_15") (pintype "passive+no_connect"))
    )
    (net (code "144") (name "unconnected-(UWB1-GPIO1-Pad14)") (class "Default")
      (node (ref "UWB1") (pin "14") (pinfunction "GPIO1_14") (pintype "passive+no_connect"))
    )
    (net (code "145") (name "unconnected-(UWB1-GPIO4-Pad11)") (class "Default")
      (node (ref "UWB1") (pin "11") (pinfunction "GPIO4_11") (pintype "passive+no_connect"))
    )
    (net (code "146") (name "unconnected-(UWB1-GPIO5-Pad10)") (class "Default")
      (node (ref "UWB1") (pin "10") (pinfunction "GPIO5_10") (pintype "passive+no_connect"))
    )
    (net (code "147") (name "unconnected-(UWB1-GPIO6-Pad9)") (class "Default")
      (node (ref "UWB1") (pin "9") (pinfunction "GPIO6_9") (pintype "passive+no_connect"))
    )
    (net (code "148") (name "unconnected-(X1-NC-Pad1)") (class "Default")
      (node (ref "X1") (pin "1") (pinfunction "NC_1") (pintype "passive+no_connect"))
    )
  )
)
